# UniversalPPU.net
KiCad netlist of a schematic drawn in EAGLE
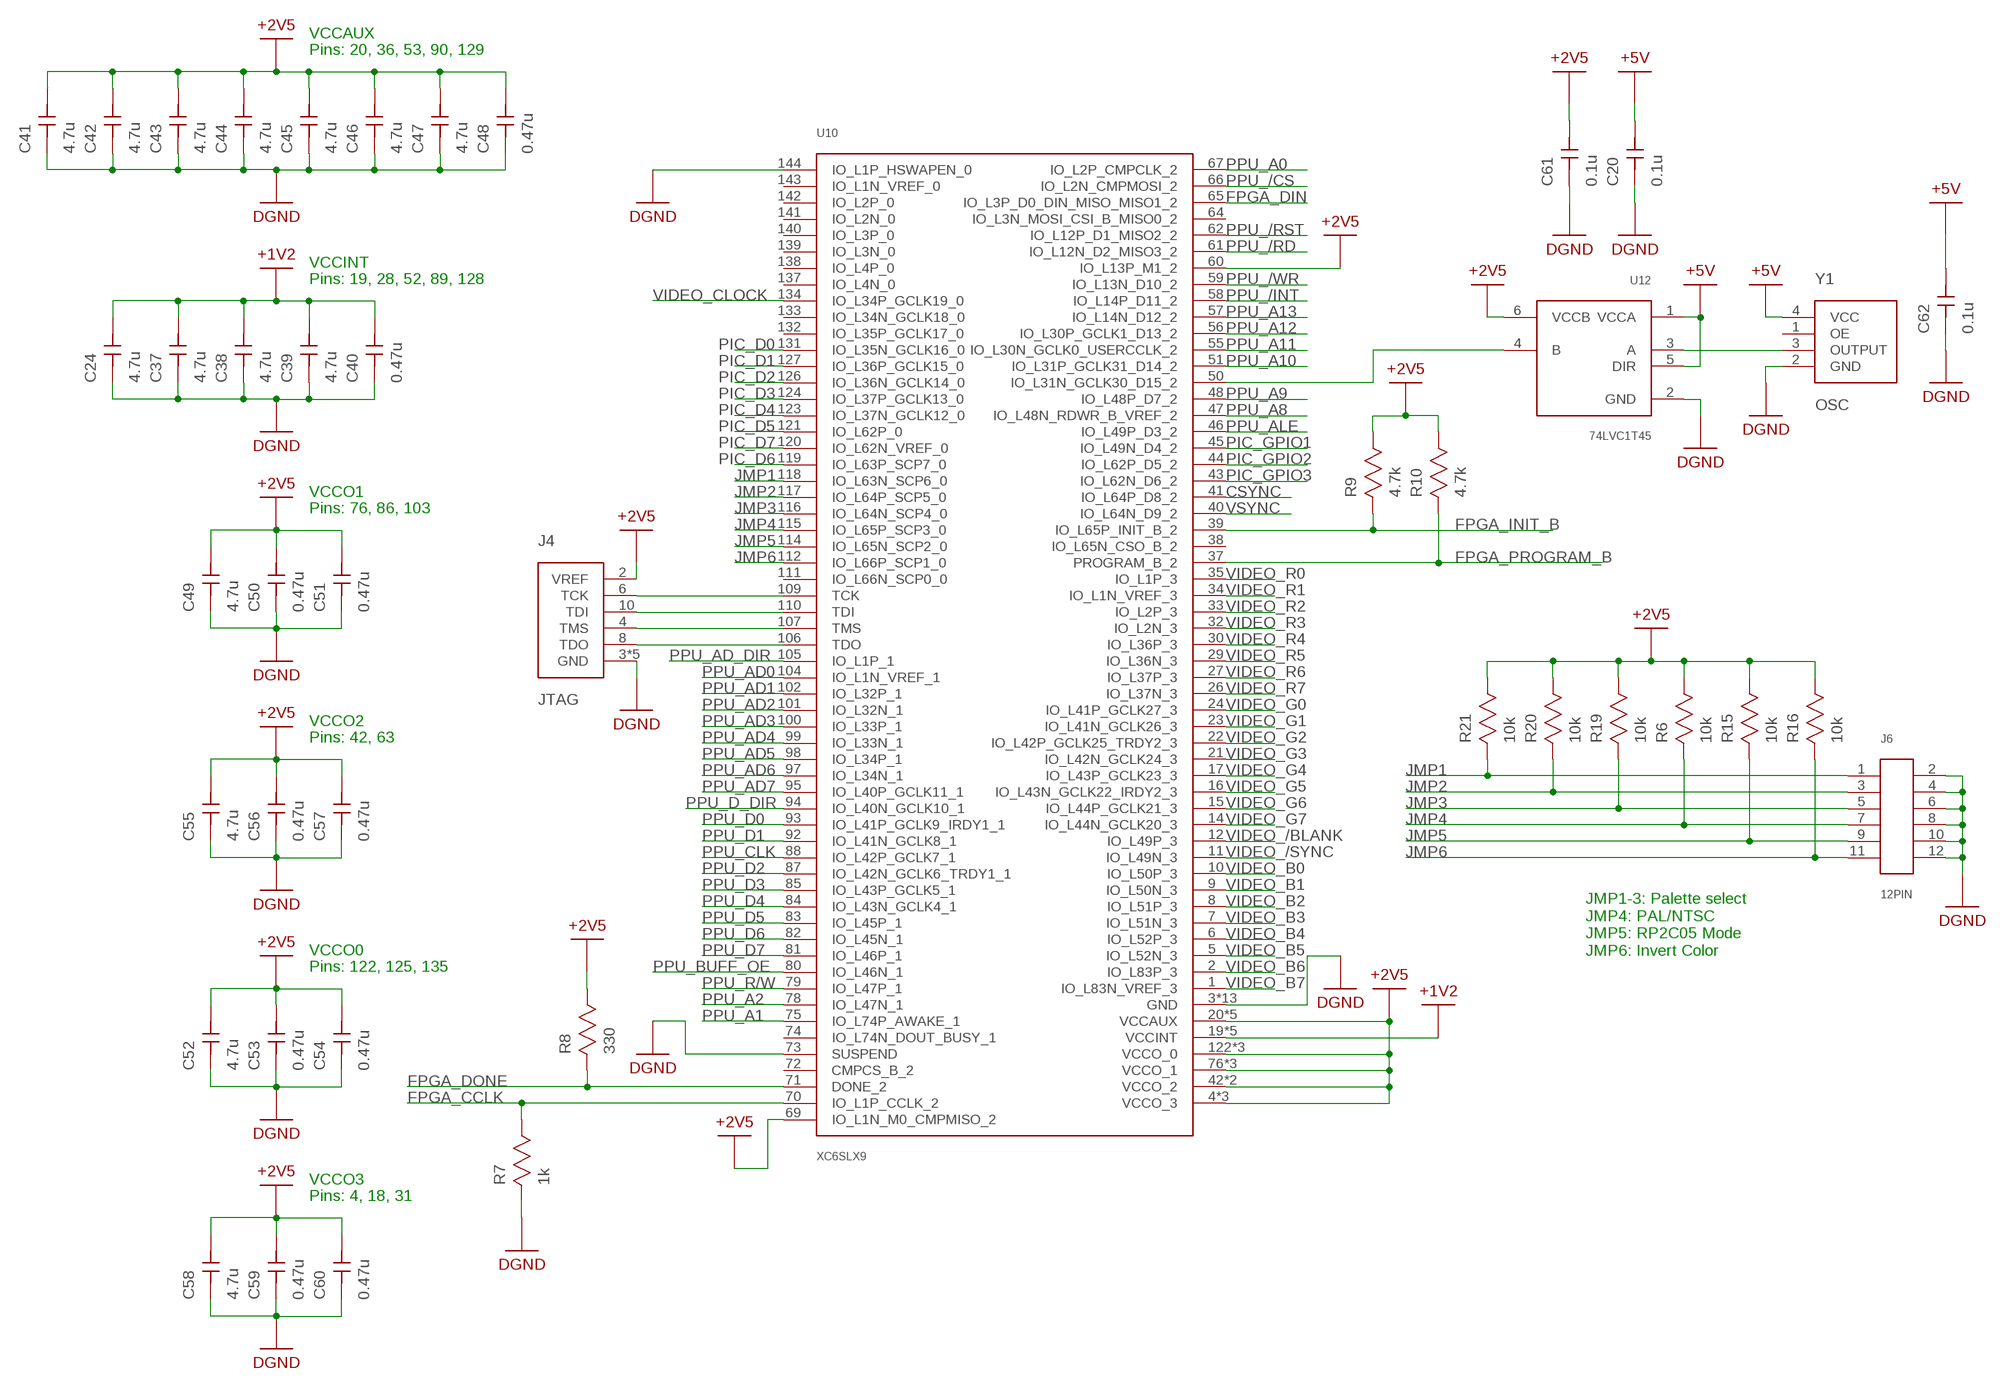
[diagram p0: schematic, sheet 1]
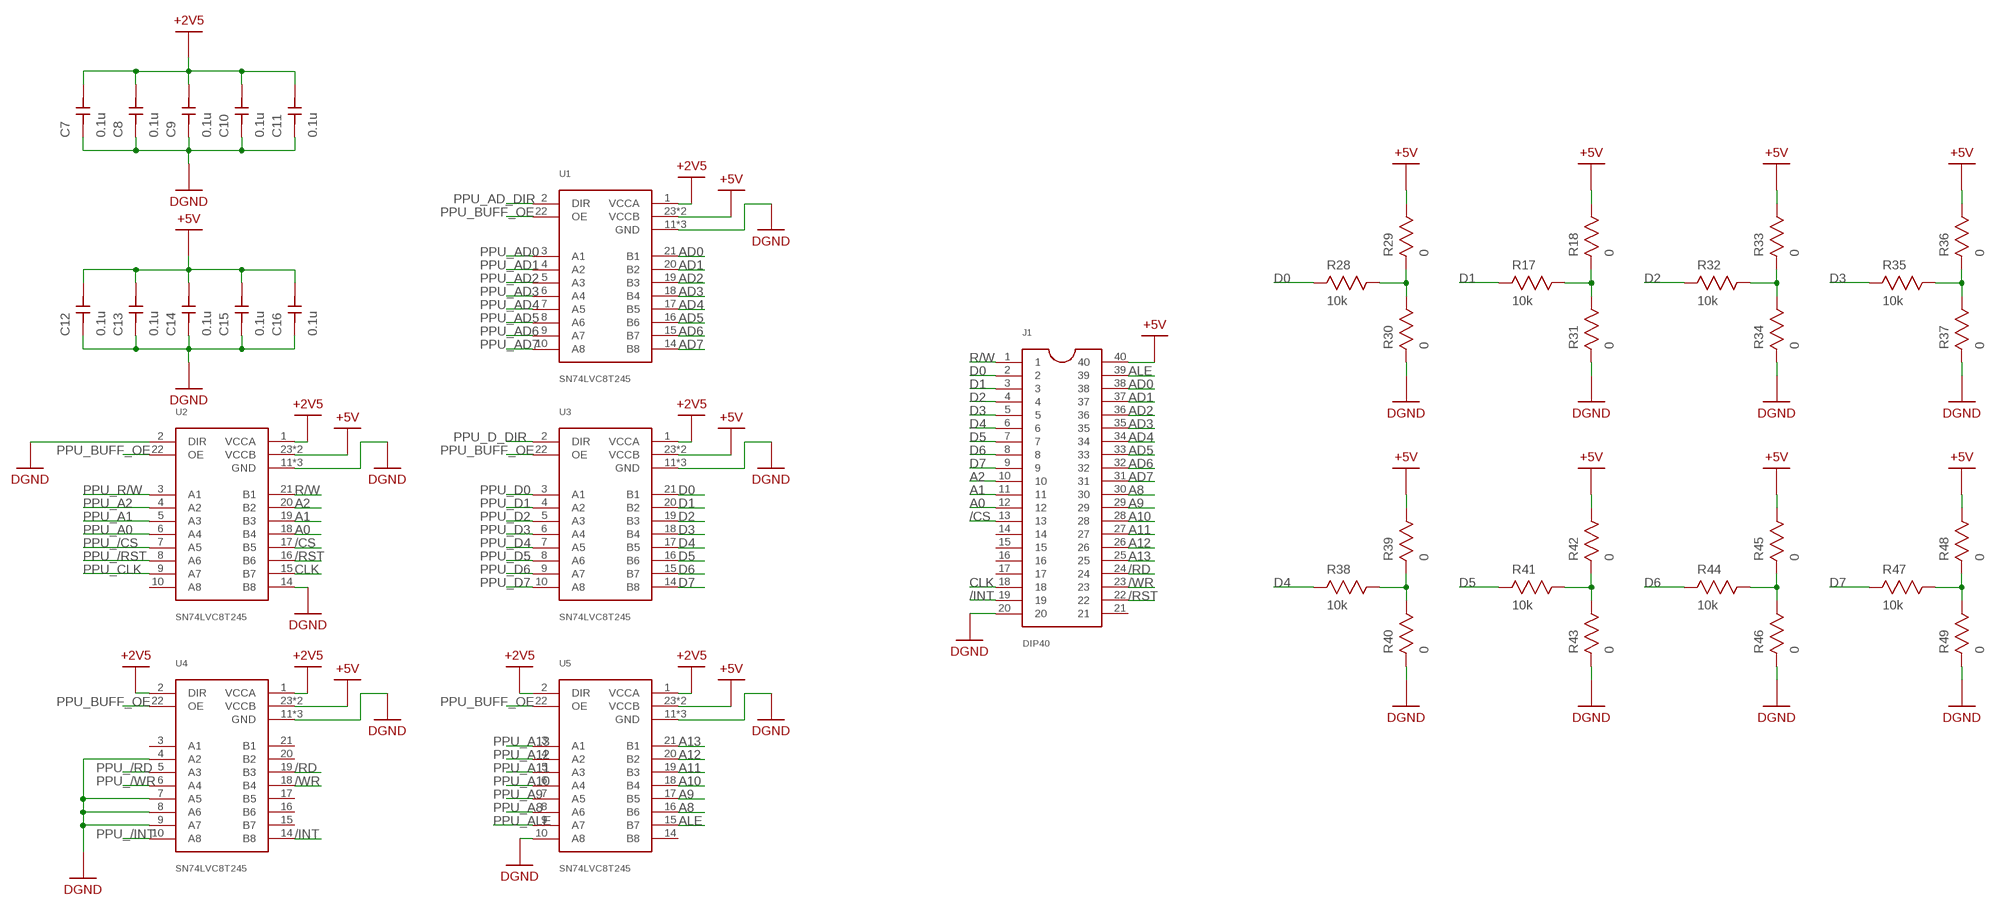
[diagram p1: schematic, sheet 2]
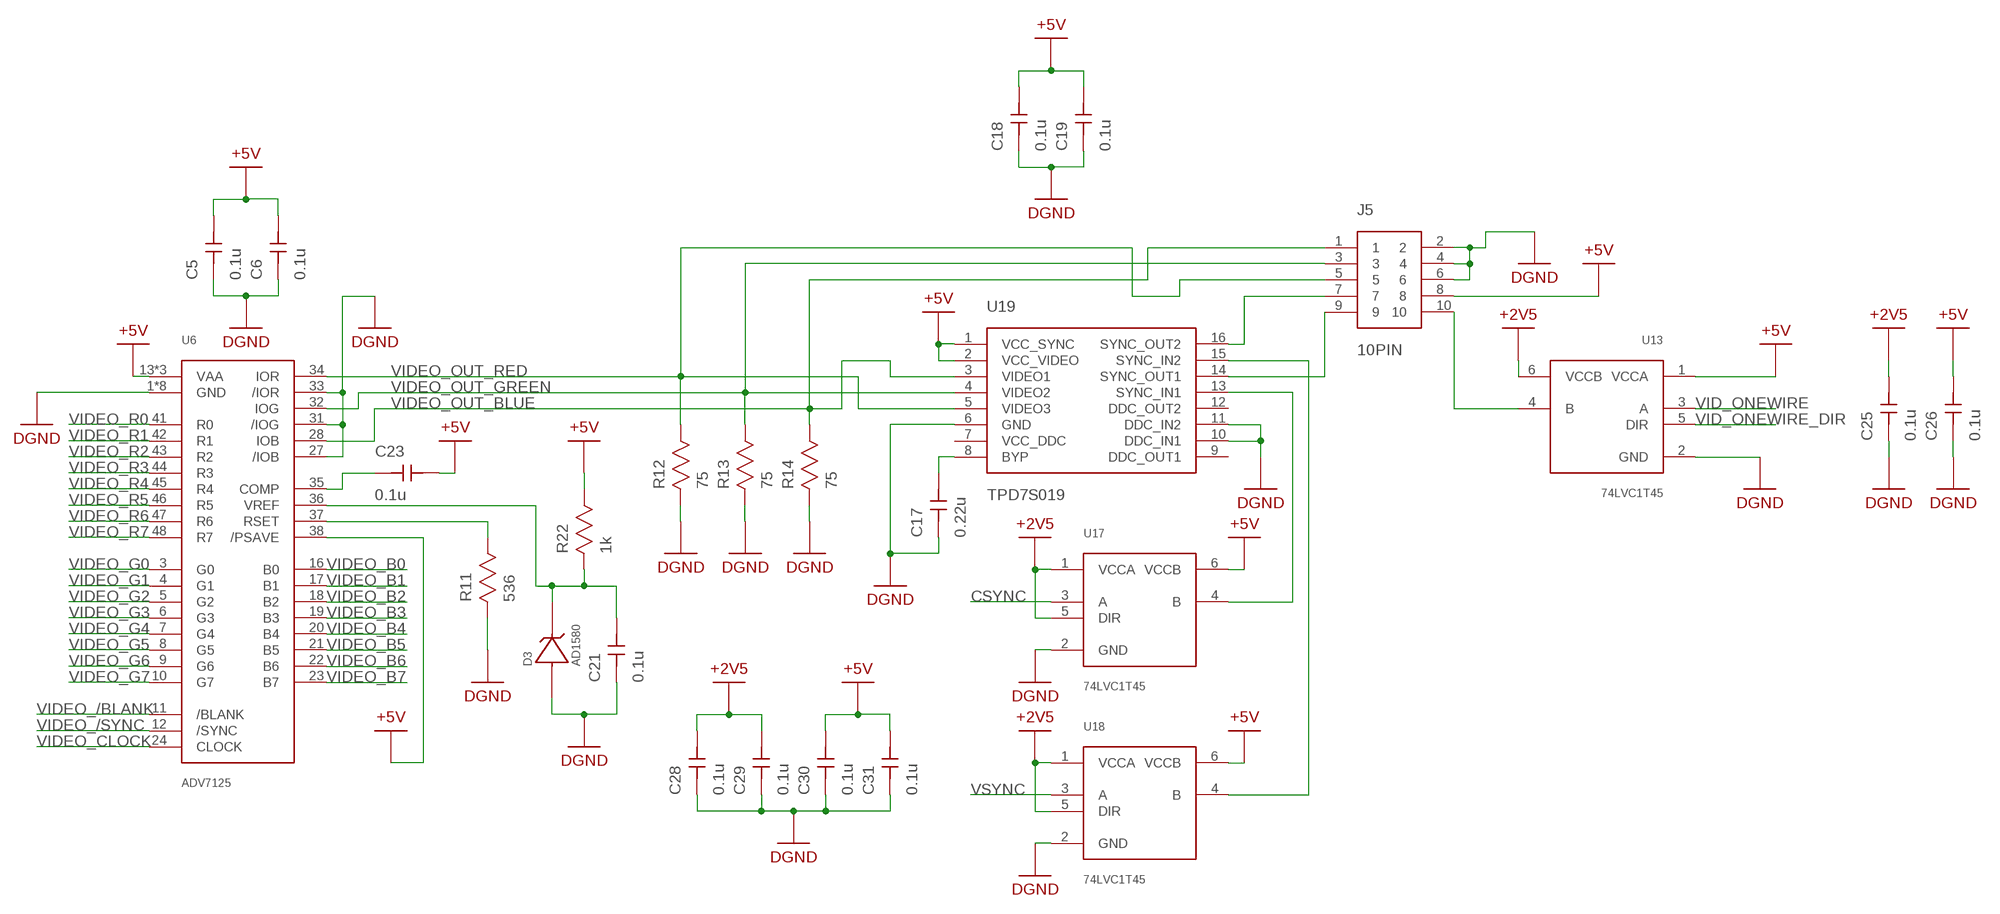
[diagram p2: schematic, sheet 3]
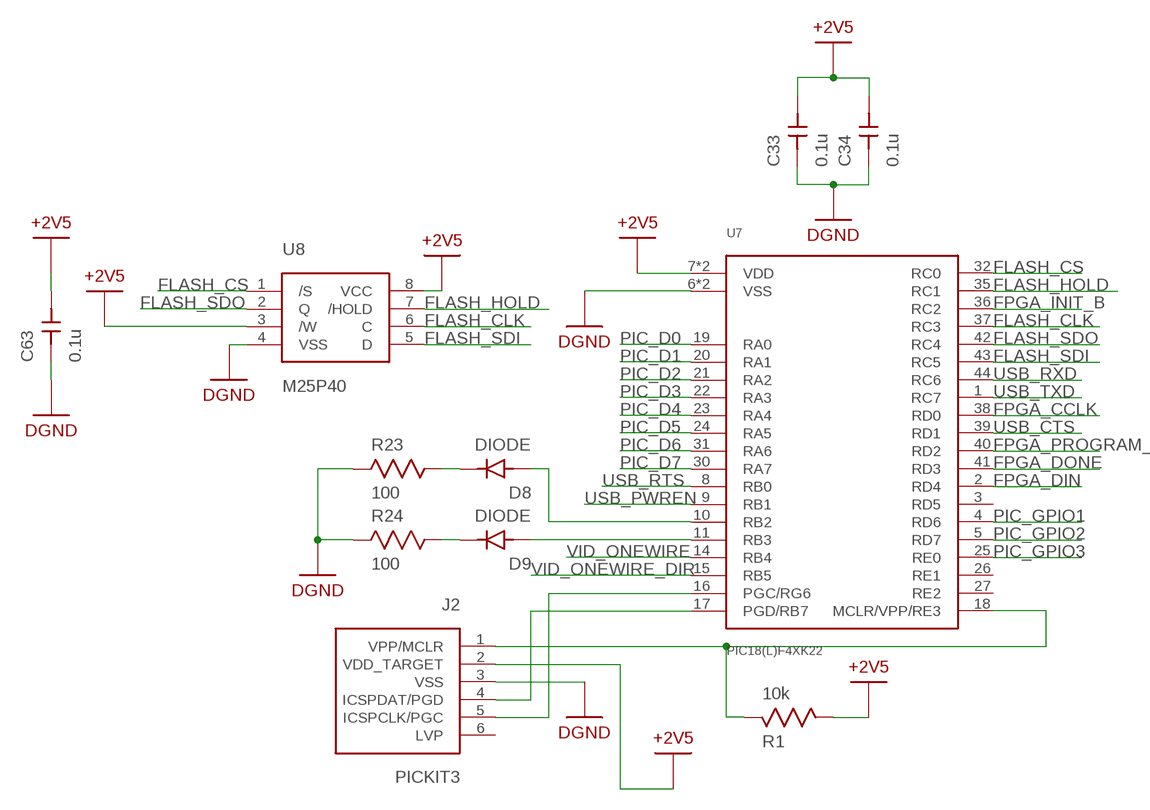
[diagram p3: schematic, sheet 4]
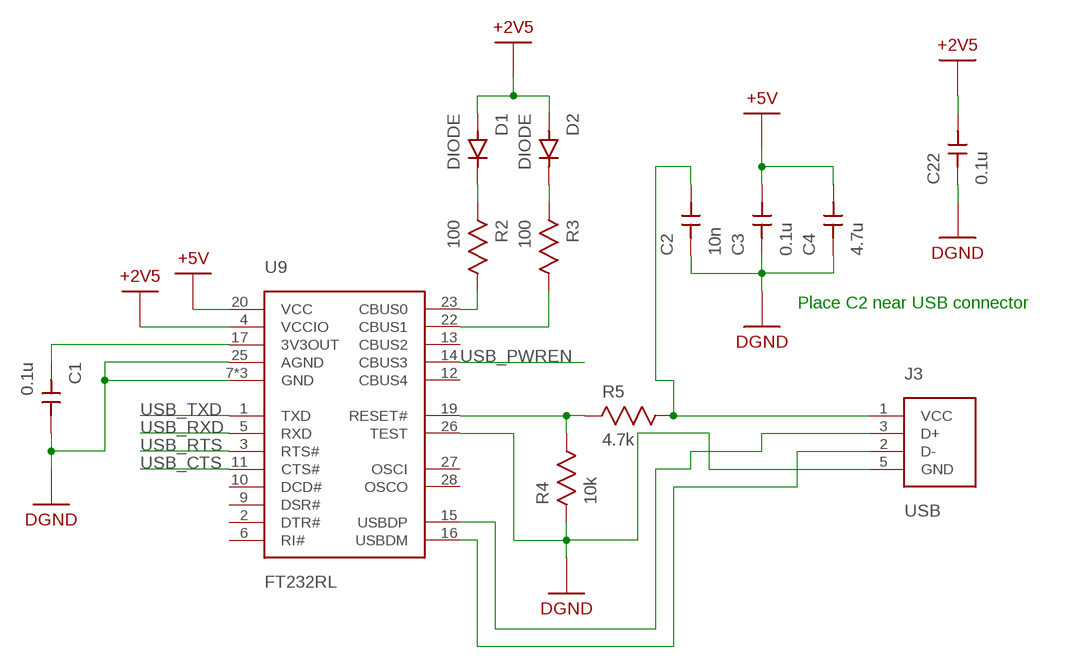
[diagram p4: schematic, sheet 5]
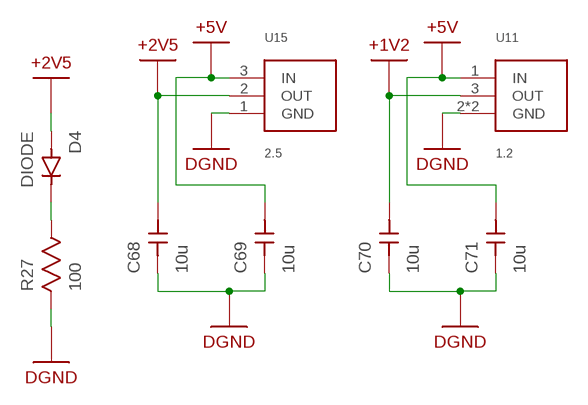
[diagram p5: schematic, sheet 6]

(export (version "E")
  (design (tool "Eeschema 10.0.6"))
  (components
    (comp (ref "C5")
      (value "0.1u")
      (footprint "eagle-import:TDK_C0816")
      (libsource (lib "eagle-import") (part "CAPACITORTDK_C0816"))
    )
    (comp (ref "C6")
      (value "0.1u")
      (footprint "eagle-import:TDK_C0816")
      (libsource (lib "eagle-import") (part "CAPACITORTDK_C0816"))
    )
    (comp (ref "C17")
      (value "0.22u")
      (footprint "eagle-import:TDK_C0816")
      (libsource (lib "eagle-import") (part "CAPACITORTDK_C0816"))
    )
    (comp (ref "C18")
      (value "0.1u")
      (footprint "eagle-import:TDK_C0816")
      (libsource (lib "eagle-import") (part "CAPACITORTDK_C0816"))
    )
    (comp (ref "C19")
      (value "0.1u")
      (footprint "eagle-import:TDK_C0816")
      (libsource (lib "eagle-import") (part "CAPACITORTDK_C0816"))
    )
    (comp (ref "C21")
      (value "0.1u")
      (footprint "eagle-import:TDK_C0816")
      (libsource (lib "eagle-import") (part "CAPACITORTDK_C0816"))
    )
    (comp (ref "C23")
      (value "0.1u")
      (footprint "eagle-import:TDK_C0816")
      (libsource (lib "eagle-import") (part "CAPACITORTDK_C0816"))
    )
    (comp (ref "C25")
      (value "0.1u")
      (footprint "eagle-import:TDK_C0816")
      (libsource (lib "eagle-import") (part "CAPACITORTDK_C0816"))
    )
    (comp (ref "C26")
      (value "0.1u")
      (footprint "eagle-import:TDK_C0816")
      (libsource (lib "eagle-import") (part "CAPACITORTDK_C0816"))
    )
    (comp (ref "C28")
      (value "0.1u")
      (footprint "eagle-import:TDK_C0816")
      (libsource (lib "eagle-import") (part "CAPACITORTDK_C0816"))
    )
    (comp (ref "C29")
      (value "0.1u")
      (footprint "eagle-import:TDK_C0816")
      (libsource (lib "eagle-import") (part "CAPACITORTDK_C0816"))
    )
    (comp (ref "C30")
      (value "0.1u")
      (footprint "eagle-import:TDK_C0816")
      (libsource (lib "eagle-import") (part "CAPACITORTDK_C0816"))
    )
    (comp (ref "C31")
      (value "0.1u")
      (footprint "eagle-import:TDK_C0816")
      (libsource (lib "eagle-import") (part "CAPACITORTDK_C0816"))
    )
    (comp (ref "D3")
      (value "AD1580")
      (footprint "eagle-import:SOT-23-3")
      (libsource (lib "eagle-import") (part "AD1580"))
    )
    (comp (ref "J5")
      (value "10PIN")
      (footprint "eagle-import:10PIN")
      (libsource (lib "eagle-import") (part "10PIN"))
    )
    (comp (ref "R11")
      (value "536")
      (footprint "eagle-import:0603")
      (libsource (lib "eagle-import") (part "RESISTOR0603"))
    )
    (comp (ref "R12")
      (value "75")
      (footprint "eagle-import:0603")
      (libsource (lib "eagle-import") (part "RESISTOR0603"))
    )
    (comp (ref "R13")
      (value "75")
      (footprint "eagle-import:0603")
      (libsource (lib "eagle-import") (part "RESISTOR0603"))
    )
    (comp (ref "R14")
      (value "75")
      (footprint "eagle-import:0603")
      (libsource (lib "eagle-import") (part "RESISTOR0603"))
    )
    (comp (ref "R22")
      (value "1k")
      (footprint "eagle-import:0603")
      (libsource (lib "eagle-import") (part "RESISTOR0603"))
    )
    (comp (ref "U6")
      (value "ADV7125")
      (footprint "eagle-import:LQFP-48")
      (libsource (lib "eagle-import") (part "ADV7125"))
    )
    (comp (ref "U13")
      (value "74LVC1T45")
      (footprint "eagle-import:R-PDSO-G6")
      (libsource (lib "eagle-import") (part "74LVC1T45"))
    )
    (comp (ref "U17")
      (value "74LVC1T45")
      (footprint "eagle-import:R-PDSO-G6")
      (libsource (lib "eagle-import") (part "74LVC1T45"))
    )
    (comp (ref "U18")
      (value "74LVC1T45")
      (footprint "eagle-import:R-PDSO-G6")
      (libsource (lib "eagle-import") (part "74LVC1T45"))
    )
    (comp (ref "U19")
      (value "TPD7S019")
      (footprint "eagle-import:R-PDSO-G16")
      (libsource (lib "eagle-import") (part "TPD7S019"))
    )
    (comp (ref "C20")
      (value "0.1u")
      (footprint "eagle-import:TDK_C0816")
      (libsource (lib "eagle-import") (part "CAPACITORTDK_C0816"))
    )
    (comp (ref "C24")
      (value "4.7u")
      (footprint "eagle-import:TDK_C0816")
      (libsource (lib "eagle-import") (part "CAPACITORTDK_C0816"))
    )
    (comp (ref "C37")
      (value "4.7u")
      (footprint "eagle-import:TDK_C0816")
      (libsource (lib "eagle-import") (part "CAPACITORTDK_C0816"))
    )
    (comp (ref "C38")
      (value "4.7u")
      (footprint "eagle-import:TDK_C0816")
      (libsource (lib "eagle-import") (part "CAPACITORTDK_C0816"))
    )
    (comp (ref "C39")
      (value "4.7u")
      (footprint "eagle-import:TDK_C0816")
      (libsource (lib "eagle-import") (part "CAPACITORTDK_C0816"))
    )
    (comp (ref "C40")
      (value "0.47u")
      (footprint "eagle-import:TDK_C0816")
      (libsource (lib "eagle-import") (part "CAPACITORTDK_C0816"))
    )
    (comp (ref "C41")
      (value "4.7u")
      (footprint "eagle-import:TDK_C0816")
      (libsource (lib "eagle-import") (part "CAPACITORTDK_C0816"))
    )
    (comp (ref "C42")
      (value "4.7u")
      (footprint "eagle-import:TDK_C0816")
      (libsource (lib "eagle-import") (part "CAPACITORTDK_C0816"))
    )
    (comp (ref "C43")
      (value "4.7u")
      (footprint "eagle-import:TDK_C0816")
      (libsource (lib "eagle-import") (part "CAPACITORTDK_C0816"))
    )
    (comp (ref "C44")
      (value "4.7u")
      (footprint "eagle-import:TDK_C0816")
      (libsource (lib "eagle-import") (part "CAPACITORTDK_C0816"))
    )
    (comp (ref "C45")
      (value "4.7u")
      (footprint "eagle-import:TDK_C0816")
      (libsource (lib "eagle-import") (part "CAPACITORTDK_C0816"))
    )
    (comp (ref "C46")
      (value "4.7u")
      (footprint "eagle-import:TDK_C0816")
      (libsource (lib "eagle-import") (part "CAPACITORTDK_C0816"))
    )
    (comp (ref "C47")
      (value "4.7u")
      (footprint "eagle-import:TDK_C0816")
      (libsource (lib "eagle-import") (part "CAPACITORTDK_C0816"))
    )
    (comp (ref "C48")
      (value "0.47u")
      (footprint "eagle-import:TDK_C0816")
      (libsource (lib "eagle-import") (part "CAPACITORTDK_C0816"))
    )
    (comp (ref "C49")
      (value "4.7u")
      (footprint "eagle-import:TDK_C0816")
      (libsource (lib "eagle-import") (part "CAPACITORTDK_C0816"))
    )
    (comp (ref "C50")
      (value "0.47u")
      (footprint "eagle-import:TDK_C0816")
      (libsource (lib "eagle-import") (part "CAPACITORTDK_C0816"))
    )
    (comp (ref "C51")
      (value "0.47u")
      (footprint "eagle-import:TDK_C0816")
      (libsource (lib "eagle-import") (part "CAPACITORTDK_C0816"))
    )
    (comp (ref "C52")
      (value "4.7u")
      (footprint "eagle-import:TDK_C0816")
      (libsource (lib "eagle-import") (part "CAPACITORTDK_C0816"))
    )
    (comp (ref "C53")
      (value "0.47u")
      (footprint "eagle-import:TDK_C0816")
      (libsource (lib "eagle-import") (part "CAPACITORTDK_C0816"))
    )
    (comp (ref "C54")
      (value "0.47u")
      (footprint "eagle-import:TDK_C0816")
      (libsource (lib "eagle-import") (part "CAPACITORTDK_C0816"))
    )
    (comp (ref "C55")
      (value "4.7u")
      (footprint "eagle-import:TDK_C0816")
      (libsource (lib "eagle-import") (part "CAPACITORTDK_C0816"))
    )
    (comp (ref "C56")
      (value "0.47u")
      (footprint "eagle-import:TDK_C0816")
      (libsource (lib "eagle-import") (part "CAPACITORTDK_C0816"))
    )
    (comp (ref "C57")
      (value "0.47u")
      (footprint "eagle-import:TDK_C0816")
      (libsource (lib "eagle-import") (part "CAPACITORTDK_C0816"))
    )
    (comp (ref "C58")
      (value "4.7u")
      (footprint "eagle-import:TDK_C0816")
      (libsource (lib "eagle-import") (part "CAPACITORTDK_C0816"))
    )
    (comp (ref "C59")
      (value "0.47u")
      (footprint "eagle-import:TDK_C0816")
      (libsource (lib "eagle-import") (part "CAPACITORTDK_C0816"))
    )
    (comp (ref "C60")
      (value "0.47u")
      (footprint "eagle-import:TDK_C0816")
      (libsource (lib "eagle-import") (part "CAPACITORTDK_C0816"))
    )
    (comp (ref "C61")
      (value "0.1u")
      (footprint "eagle-import:TDK_C0816")
      (libsource (lib "eagle-import") (part "CAPACITORTDK_C0816"))
    )
    (comp (ref "C62")
      (value "0.1u")
      (footprint "eagle-import:TDK_C0816")
      (libsource (lib "eagle-import") (part "CAPACITORTDK_C0816"))
    )
    (comp (ref "J4")
      (value "JTAG")
      (footprint "eagle-import:14PIN_2MM")
      (libsource (lib "eagle-import") (part "JTAG"))
    )
    (comp (ref "J6")
      (value "12PIN")
      (footprint "eagle-import:12PIN")
      (libsource (lib "eagle-import") (part "12PIN"))
    )
    (comp (ref "R6")
      (value "10k")
      (footprint "eagle-import:0603")
      (libsource (lib "eagle-import") (part "RESISTOR0603"))
    )
    (comp (ref "R7")
      (value "1k")
      (footprint "eagle-import:0603")
      (libsource (lib "eagle-import") (part "RESISTOR0603"))
    )
    (comp (ref "R8")
      (value "330")
      (footprint "eagle-import:0603")
      (libsource (lib "eagle-import") (part "RESISTOR0603"))
    )
    (comp (ref "R9")
      (value "4.7k")
      (footprint "eagle-import:0603")
      (libsource (lib "eagle-import") (part "RESISTOR0603"))
    )
    (comp (ref "R10")
      (value "4.7k")
      (footprint "eagle-import:0603")
      (libsource (lib "eagle-import") (part "RESISTOR0603"))
    )
    (comp (ref "R15")
      (value "10k")
      (footprint "eagle-import:0603")
      (libsource (lib "eagle-import") (part "RESISTOR0603"))
    )
    (comp (ref "R16")
      (value "10k")
      (footprint "eagle-import:0603")
      (libsource (lib "eagle-import") (part "RESISTOR0603"))
    )
    (comp (ref "R19")
      (value "10k")
      (footprint "eagle-import:0603")
      (libsource (lib "eagle-import") (part "RESISTOR0603"))
    )
    (comp (ref "R20")
      (value "10k")
      (footprint "eagle-import:0603")
      (libsource (lib "eagle-import") (part "RESISTOR0603"))
    )
    (comp (ref "R21")
      (value "10k")
      (footprint "eagle-import:0603")
      (libsource (lib "eagle-import") (part "RESISTOR0603"))
    )
    (comp (ref "U10")
      (value "XC6SLX9")
      (footprint "eagle-import:TQG144")
      (libsource (lib "eagle-import") (part "XC6SLX9"))
    )
    (comp (ref "U12")
      (value "74LVC1T45")
      (footprint "eagle-import:R-PDSO-G6")
      (libsource (lib "eagle-import") (part "74LVC1T45"))
    )
    (comp (ref "Y1")
      (value "OSC")
      (footprint "eagle-import:OSC")
      (libsource (lib "eagle-import") (part "OSC"))
    )
    (comp (ref "C68")
      (value "10u")
      (footprint "eagle-import:TDK_C1632")
      (libsource (lib "eagle-import") (part "CAPACITORTDK_C1632"))
    )
    (comp (ref "C69")
      (value "10u")
      (footprint "eagle-import:TDK_C1632")
      (libsource (lib "eagle-import") (part "CAPACITORTDK_C1632"))
    )
    (comp (ref "C70")
      (value "10u")
      (footprint "eagle-import:TDK_C1632")
      (libsource (lib "eagle-import") (part "CAPACITORTDK_C1632"))
    )
    (comp (ref "C71")
      (value "10u")
      (footprint "eagle-import:TDK_C1632")
      (libsource (lib "eagle-import") (part "CAPACITORTDK_C1632"))
    )
    (comp (ref "D4")
      (value "DIODE")
      (footprint "eagle-import:LED_0603")
      (libsource (lib "eagle-import") (part "DIODE"))
    )
    (comp (ref "R27")
      (value "100")
      (footprint "eagle-import:0603")
      (libsource (lib "eagle-import") (part "RESISTOR0603"))
    )
    (comp (ref "U11")
      (value "1.2")
      (footprint "eagle-import:SOT-223")
      (libsource (lib "eagle-import") (part "NCP566"))
    )
    (comp (ref "U15")
      (value "2.5")
      (footprint "eagle-import:SOT-223")
      (libsource (lib "eagle-import") (part "NCP1117"))
    )
    (comp (ref "C7")
      (value "0.1u")
      (footprint "eagle-import:TDK_C0816")
      (libsource (lib "eagle-import") (part "CAPACITORTDK_C0816"))
    )
    (comp (ref "C8")
      (value "0.1u")
      (footprint "eagle-import:TDK_C0816")
      (libsource (lib "eagle-import") (part "CAPACITORTDK_C0816"))
    )
    (comp (ref "C9")
      (value "0.1u")
      (footprint "eagle-import:TDK_C0816")
      (libsource (lib "eagle-import") (part "CAPACITORTDK_C0816"))
    )
    (comp (ref "C10")
      (value "0.1u")
      (footprint "eagle-import:TDK_C0816")
      (libsource (lib "eagle-import") (part "CAPACITORTDK_C0816"))
    )
    (comp (ref "C11")
      (value "0.1u")
      (footprint "eagle-import:TDK_C0816")
      (libsource (lib "eagle-import") (part "CAPACITORTDK_C0816"))
    )
    (comp (ref "C12")
      (value "0.1u")
      (footprint "eagle-import:TDK_C0816")
      (libsource (lib "eagle-import") (part "CAPACITORTDK_C0816"))
    )
    (comp (ref "C13")
      (value "0.1u")
      (footprint "eagle-import:TDK_C0816")
      (libsource (lib "eagle-import") (part "CAPACITORTDK_C0816"))
    )
    (comp (ref "C14")
      (value "0.1u")
      (footprint "eagle-import:TDK_C0816")
      (libsource (lib "eagle-import") (part "CAPACITORTDK_C0816"))
    )
    (comp (ref "C15")
      (value "0.1u")
      (footprint "eagle-import:TDK_C0816")
      (libsource (lib "eagle-import") (part "CAPACITORTDK_C0816"))
    )
    (comp (ref "C16")
      (value "0.1u")
      (footprint "eagle-import:TDK_C0816")
      (libsource (lib "eagle-import") (part "CAPACITORTDK_C0816"))
    )
    (comp (ref "J1")
      (value "DIP40")
      (footprint "eagle-import:DIP40")
      (libsource (lib "eagle-import") (part "DIP40"))
    )
    (comp (ref "R17")
      (value "10k")
      (footprint "eagle-import:0603")
      (libsource (lib "eagle-import") (part "RESISTOR0603"))
    )
    (comp (ref "R18")
      (value "0")
      (footprint "eagle-import:0603")
      (libsource (lib "eagle-import") (part "RESISTOR0603"))
    )
    (comp (ref "R28")
      (value "10k")
      (footprint "eagle-import:0603")
      (libsource (lib "eagle-import") (part "RESISTOR0603"))
    )
    (comp (ref "R29")
      (value "0")
      (footprint "eagle-import:0603")
      (libsource (lib "eagle-import") (part "RESISTOR0603"))
    )
    (comp (ref "R30")
      (value "0")
      (footprint "eagle-import:0603")
      (libsource (lib "eagle-import") (part "RESISTOR0603"))
    )
    (comp (ref "R31")
      (value "0")
      (footprint "eagle-import:0603")
      (libsource (lib "eagle-import") (part "RESISTOR0603"))
    )
    (comp (ref "R32")
      (value "10k")
      (footprint "eagle-import:0603")
      (libsource (lib "eagle-import") (part "RESISTOR0603"))
    )
    (comp (ref "R33")
      (value "0")
      (footprint "eagle-import:0603")
      (libsource (lib "eagle-import") (part "RESISTOR0603"))
    )
    (comp (ref "R34")
      (value "0")
      (footprint "eagle-import:0603")
      (libsource (lib "eagle-import") (part "RESISTOR0603"))
    )
    (comp (ref "R35")
      (value "10k")
      (footprint "eagle-import:0603")
      (libsource (lib "eagle-import") (part "RESISTOR0603"))
    )
    (comp (ref "R36")
      (value "0")
      (footprint "eagle-import:0603")
      (libsource (lib "eagle-import") (part "RESISTOR0603"))
    )
    (comp (ref "R37")
      (value "0")
      (footprint "eagle-import:0603")
      (libsource (lib "eagle-import") (part "RESISTOR0603"))
    )
    (comp (ref "R38")
      (value "10k")
      (footprint "eagle-import:0603")
      (libsource (lib "eagle-import") (part "RESISTOR0603"))
    )
    (comp (ref "R39")
      (value "0")
      (footprint "eagle-import:0603")
      (libsource (lib "eagle-import") (part "RESISTOR0603"))
    )
    (comp (ref "R40")
      (value "0")
      (footprint "eagle-import:0603")
      (libsource (lib "eagle-import") (part "RESISTOR0603"))
    )
    (comp (ref "R41")
      (value "10k")
      (footprint "eagle-import:0603")
      (libsource (lib "eagle-import") (part "RESISTOR0603"))
    )
    (comp (ref "R42")
      (value "0")
      (footprint "eagle-import:0603")
      (libsource (lib "eagle-import") (part "RESISTOR0603"))
    )
    (comp (ref "R43")
      (value "0")
      (footprint "eagle-import:0603")
      (libsource (lib "eagle-import") (part "RESISTOR0603"))
    )
    (comp (ref "R44")
      (value "10k")
      (footprint "eagle-import:0603")
      (libsource (lib "eagle-import") (part "RESISTOR0603"))
    )
    (comp (ref "R45")
      (value "0")
      (footprint "eagle-import:0603")
      (libsource (lib "eagle-import") (part "RESISTOR0603"))
    )
    (comp (ref "R46")
      (value "0")
      (footprint "eagle-import:0603")
      (libsource (lib "eagle-import") (part "RESISTOR0603"))
    )
    (comp (ref "R47")
      (value "10k")
      (footprint "eagle-import:0603")
      (libsource (lib "eagle-import") (part "RESISTOR0603"))
    )
    (comp (ref "R48")
      (value "0")
      (footprint "eagle-import:0603")
      (libsource (lib "eagle-import") (part "RESISTOR0603"))
    )
    (comp (ref "R49")
      (value "0")
      (footprint "eagle-import:0603")
      (libsource (lib "eagle-import") (part "RESISTOR0603"))
    )
    (comp (ref "U1")
      (value "SN74LVC8T245")
      (footprint "eagle-import:TSSOP24")
      (libsource (lib "eagle-import") (part "SN74LVC8T245"))
    )
    (comp (ref "U2")
      (value "SN74LVC8T245")
      (footprint "eagle-import:TSSOP24")
      (libsource (lib "eagle-import") (part "SN74LVC8T245"))
    )
    (comp (ref "U3")
      (value "SN74LVC8T245")
      (footprint "eagle-import:TSSOP24")
      (libsource (lib "eagle-import") (part "SN74LVC8T245"))
    )
    (comp (ref "U4")
      (value "SN74LVC8T245")
      (footprint "eagle-import:TSSOP24")
      (libsource (lib "eagle-import") (part "SN74LVC8T245"))
    )
    (comp (ref "U5")
      (value "SN74LVC8T245")
      (footprint "eagle-import:TSSOP24")
      (libsource (lib "eagle-import") (part "SN74LVC8T245"))
    )
    (comp (ref "C1")
      (value "0.1u")
      (footprint "eagle-import:TDK_C0816")
      (libsource (lib "eagle-import") (part "CAPACITORTDK_C0816"))
    )
    (comp (ref "C2")
      (value "10n")
      (footprint "eagle-import:TDK_C0816")
      (libsource (lib "eagle-import") (part "CAPACITORTDK_C0816"))
    )
    (comp (ref "C3")
      (value "0.1u")
      (footprint "eagle-import:TDK_C0816")
      (libsource (lib "eagle-import") (part "CAPACITORTDK_C0816"))
    )
    (comp (ref "C4")
      (value "4.7u")
      (footprint "eagle-import:TDK_C0816")
      (libsource (lib "eagle-import") (part "CAPACITORTDK_C0816"))
    )
    (comp (ref "C22")
      (value "0.1u")
      (footprint "eagle-import:TDK_C0816")
      (libsource (lib "eagle-import") (part "CAPACITORTDK_C0816"))
    )
    (comp (ref "D1")
      (value "DIODE")
      (footprint "eagle-import:LED_0603")
      (libsource (lib "eagle-import") (part "DIODE"))
    )
    (comp (ref "D2")
      (value "DIODE")
      (footprint "eagle-import:LED_0603")
      (libsource (lib "eagle-import") (part "DIODE"))
    )
    (comp (ref "J3")
      (value "USB")
      (footprint "eagle-import:USB")
      (libsource (lib "eagle-import") (part "USB"))
    )
    (comp (ref "R2")
      (value "100")
      (footprint "eagle-import:0603")
      (libsource (lib "eagle-import") (part "RESISTOR0603"))
    )
    (comp (ref "R3")
      (value "100")
      (footprint "eagle-import:0603")
      (libsource (lib "eagle-import") (part "RESISTOR0603"))
    )
    (comp (ref "R4")
      (value "10k")
      (footprint "eagle-import:0603")
      (libsource (lib "eagle-import") (part "RESISTOR0603"))
    )
    (comp (ref "R5")
      (value "4.7k")
      (footprint "eagle-import:0603")
      (libsource (lib "eagle-import") (part "RESISTOR0603"))
    )
    (comp (ref "U9")
      (value "FT232RL")
      (footprint "eagle-import:SSOP-28")
      (libsource (lib "eagle-import") (part "FT232RL"))
    )
    (comp (ref "C33")
      (value "0.1u")
      (footprint "eagle-import:TDK_C0816")
      (libsource (lib "eagle-import") (part "CAPACITORTDK_C0816"))
    )
    (comp (ref "C34")
      (value "0.1u")
      (footprint "eagle-import:TDK_C0816")
      (libsource (lib "eagle-import") (part "CAPACITORTDK_C0816"))
    )
    (comp (ref "C63")
      (value "0.1u")
      (footprint "eagle-import:TDK_C0816")
      (libsource (lib "eagle-import") (part "CAPACITORTDK_C0816"))
    )
    (comp (ref "D8")
      (value "DIODE")
      (footprint "eagle-import:LED_0603")
      (libsource (lib "eagle-import") (part "DIODE"))
    )
    (comp (ref "D9")
      (value "DIODE")
      (footprint "eagle-import:LED_0603")
      (libsource (lib "eagle-import") (part "DIODE"))
    )
    (comp (ref "J2")
      (value "PICKIT3")
      (footprint "eagle-import:6SIP")
      (libsource (lib "eagle-import") (part "PICKIT3"))
    )
    (comp (ref "R1")
      (value "10k")
      (footprint "eagle-import:0603")
      (libsource (lib "eagle-import") (part "RESISTOR0603"))
    )
    (comp (ref "R23")
      (value "100")
      (footprint "eagle-import:0603")
      (libsource (lib "eagle-import") (part "RESISTOR0603"))
    )
    (comp (ref "R24")
      (value "100")
      (footprint "eagle-import:0603")
      (libsource (lib "eagle-import") (part "RESISTOR0603"))
    )
    (comp (ref "U7")
      (value "PIC18(L)F4XK22")
      (footprint "eagle-import:TQFP44")
      (libsource (lib "eagle-import") (part "PIC18(L)F4XK22"))
    )
    (comp (ref "U8")
      (value "M25P40")
      (footprint "eagle-import:8PIN")
      (libsource (lib "eagle-import") (part "M25P40"))
    )
  )
  (nets
    (net (code "1") (name "+1V2") (class "Default")
      (node (ref "C24") (pin "2") (pinfunction "P$2_2") (pintype "bidirectional"))
      (node (ref "C37") (pin "2") (pinfunction "P$2_2") (pintype "bidirectional"))
      (node (ref "C38") (pin "2") (pinfunction "P$2_2") (pintype "bidirectional"))
      (node (ref "C39") (pin "2") (pinfunction "P$2_2") (pintype "bidirectional"))
      (node (ref "C40") (pin "2") (pinfunction "P$2_2") (pintype "bidirectional"))
      (node (ref "C70") (pin "2") (pinfunction "P$2_2") (pintype "bidirectional"))
      (node (ref "U10") (pin "128") (pinfunction "VCCINT_128") (pintype "bidirectional"))
      (node (ref "U10") (pin "19") (pinfunction "VCCINT_19") (pintype "bidirectional"))
      (node (ref "U10") (pin "28") (pinfunction "VCCINT_28") (pintype "bidirectional"))
      (node (ref "U10") (pin "52") (pinfunction "VCCINT_52") (pintype "bidirectional"))
      (node (ref "U10") (pin "89") (pinfunction "VCCINT_89") (pintype "bidirectional"))
      (node (ref "U11") (pin "3") (pinfunction "OUT_3") (pintype "bidirectional"))
    )
    (net (code "2") (name "+2V5") (class "Default")
      (node (ref "C10") (pin "2") (pinfunction "P$2_2") (pintype "bidirectional"))
      (node (ref "C11") (pin "2") (pinfunction "P$2_2") (pintype "bidirectional"))
      (node (ref "C22") (pin "2") (pinfunction "P$2_2") (pintype "bidirectional"))
      (node (ref "C25") (pin "2") (pinfunction "P$2_2") (pintype "bidirectional"))
      (node (ref "C28") (pin "2") (pinfunction "P$2_2") (pintype "bidirectional"))
      (node (ref "C29") (pin "2") (pinfunction "P$2_2") (pintype "bidirectional"))
      (node (ref "C33") (pin "2") (pinfunction "P$2_2") (pintype "bidirectional"))
      (node (ref "C34") (pin "2") (pinfunction "P$2_2") (pintype "bidirectional"))
      (node (ref "C41") (pin "2") (pinfunction "P$2_2") (pintype "bidirectional"))
      (node (ref "C42") (pin "2") (pinfunction "P$2_2") (pintype "bidirectional"))
      (node (ref "C43") (pin "2") (pinfunction "P$2_2") (pintype "bidirectional"))
      (node (ref "C44") (pin "2") (pinfunction "P$2_2") (pintype "bidirectional"))
      (node (ref "C45") (pin "2") (pinfunction "P$2_2") (pintype "bidirectional"))
      (node (ref "C46") (pin "2") (pinfunction "P$2_2") (pintype "bidirectional"))
      (node (ref "C47") (pin "2") (pinfunction "P$2_2") (pintype "bidirectional"))
      (node (ref "C48") (pin "2") (pinfunction "P$2_2") (pintype "bidirectional"))
      (node (ref "C49") (pin "2") (pinfunction "P$2_2") (pintype "bidirectional"))
      (node (ref "C50") (pin "2") (pinfunction "P$2_2") (pintype "bidirectional"))
      (node (ref "C51") (pin "2") (pinfunction "P$2_2") (pintype "bidirectional"))
      (node (ref "C52") (pin "2") (pinfunction "P$2_2") (pintype "bidirectional"))
      (node (ref "C53") (pin "2") (pinfunction "P$2_2") (pintype "bidirectional"))
      (node (ref "C54") (pin "2") (pinfunction "P$2_2") (pintype "bidirectional"))
      (node (ref "C55") (pin "2") (pinfunction "P$2_2") (pintype "bidirectional"))
      (node (ref "C56") (pin "2") (pinfunction "P$2_2") (pintype "bidirectional"))
      (node (ref "C57") (pin "2") (pinfunction "P$2_2") (pintype "bidirectional"))
      (node (ref "C58") (pin "2") (pinfunction "P$2_2") (pintype "bidirectional"))
      (node (ref "C59") (pin "2") (pinfunction "P$2_2") (pintype "bidirectional"))
      (node (ref "C60") (pin "2") (pinfunction "P$2_2") (pintype "bidirectional"))
      (node (ref "C61") (pin "2") (pinfunction "P$2_2") (pintype "bidirectional"))
      (node (ref "C63") (pin "2") (pinfunction "P$2_2") (pintype "bidirectional"))
      (node (ref "C68") (pin "2") (pinfunction "P$2_2") (pintype "bidirectional"))
      (node (ref "C7") (pin "2") (pinfunction "P$2_2") (pintype "bidirectional"))
      (node (ref "C8") (pin "2") (pinfunction "P$2_2") (pintype "bidirectional"))
      (node (ref "C9") (pin "2") (pinfunction "P$2_2") (pintype "bidirectional"))
      (node (ref "D1") (pin "A") (pinfunction "A_A") (pintype "bidirectional"))
      (node (ref "D2") (pin "A") (pinfunction "A_A") (pintype "bidirectional"))
      (node (ref "D4") (pin "A") (pinfunction "A_A") (pintype "bidirectional"))
      (node (ref "J2") (pin "2") (pinfunction "VDD_TARGET_2") (pintype "bidirectional"))
      (node (ref "J4") (pin "2") (pinfunction "VREF_2") (pintype "bidirectional"))
      (node (ref "R1") (pin "P$2") (pinfunction "P$2_P$2") (pintype "bidirectional"))
      (node (ref "R10") (pin "P$2") (pinfunction "P$2_P$2") (pintype "bidirectional"))
      (node (ref "R15") (pin "P$2") (pinfunction "P$2_P$2") (pintype "bidirectional"))
      (node (ref "R16") (pin "P$2") (pinfunction "P$2_P$2") (pintype "bidirectional"))
      (node (ref "R19") (pin "P$2") (pinfunction "P$2_P$2") (pintype "bidirectional"))
      (node (ref "R20") (pin "P$2") (pinfunction "P$2_P$2") (pintype "bidirectional"))
      (node (ref "R21") (pin "P$2") (pinfunction "P$2_P$2") (pintype "bidirectional"))
      (node (ref "R6") (pin "P$2") (pinfunction "P$2_P$2") (pintype "bidirectional"))
      (node (ref "R8") (pin "P$2") (pinfunction "P$2_P$2") (pintype "bidirectional"))
      (node (ref "R9") (pin "P$2") (pinfunction "P$2_P$2") (pintype "bidirectional"))
      (node (ref "U1") (pin "1") (pinfunction "VCCA_1") (pintype "bidirectional"))
      (node (ref "U10") (pin "103") (pinfunction "VCCO_1_103") (pintype "bidirectional"))
      (node (ref "U10") (pin "122") (pinfunction "VCCO_0_122") (pintype "bidirectional"))
      (node (ref "U10") (pin "125") (pinfunction "VCCO_0_125") (pintype "bidirectional"))
      (node (ref "U10") (pin "129") (pinfunction "VCCAUX_129") (pintype "bidirectional"))
      (node (ref "U10") (pin "135") (pinfunction "VCCO_0_135") (pintype "bidirectional"))
      (node (ref "U10") (pin "18") (pinfunction "VCCO_3_18") (pintype "bidirectional"))
      (node (ref "U10") (pin "20") (pinfunction "VCCAUX_20") (pintype "bidirectional"))
      (node (ref "U10") (pin "31") (pinfunction "VCCO_3_31") (pintype "bidirectional"))
      (node (ref "U10") (pin "36") (pinfunction "VCCAUX_36") (pintype "bidirectional"))
      (node (ref "U10") (pin "4") (pinfunction "VCCO_3_4") (pintype "bidirectional"))
      (node (ref "U10") (pin "42") (pinfunction "VCCO_2_42") (pintype "bidirectional"))
      (node (ref "U10") (pin "53") (pinfunction "VCCAUX_53") (pintype "bidirectional"))
      (node (ref "U10") (pin "60") (pinfunction "IO_L13P_M1_2_60") (pintype "bidirectional"))
      (node (ref "U10") (pin "63") (pinfunction "VCCO_2_63") (pintype "bidirectional"))
      (node (ref "U10") (pin "69") (pinfunction "IO_L1N_M0_CMPMISO_2_69") (pintype "bidirectional"))
      (node (ref "U10") (pin "76") (pinfunction "VCCO_1_76") (pintype "bidirectional"))
      (node (ref "U10") (pin "86") (pinfunction "VCCO_1_86") (pintype "bidirectional"))
      (node (ref "U10") (pin "90") (pinfunction "VCCAUX_90") (pintype "bidirectional"))
      (node (ref "U12") (pin "6") (pinfunction "VCCB_6") (pintype "bidirectional"))
      (node (ref "U13") (pin "6") (pinfunction "VCCB_6") (pintype "bidirectional"))
      (node (ref "U15") (pin "2") (pinfunction "OUT_2") (pintype "bidirectional"))
      (node (ref "U17") (pin "1") (pinfunction "VCCA_1") (pintype "bidirectional"))
      (node (ref "U17") (pin "5") (pinfunction "DIR_5") (pintype "bidirectional"))
      (node (ref "U18") (pin "1") (pinfunction "VCCA_1") (pintype "bidirectional"))
      (node (ref "U18") (pin "5") (pinfunction "DIR_5") (pintype "bidirectional"))
      (node (ref "U2") (pin "1") (pinfunction "VCCA_1") (pintype "bidirectional"))
      (node (ref "U3") (pin "1") (pinfunction "VCCA_1") (pintype "bidirectional"))
      (node (ref "U4") (pin "1") (pinfunction "VCCA_1") (pintype "bidirectional"))
      (node (ref "U4") (pin "2") (pinfunction "DIR_2") (pintype "bidirectional"))
      (node (ref "U5") (pin "1") (pinfunction "VCCA_1") (pintype "bidirectional"))
      (node (ref "U5") (pin "2") (pinfunction "DIR_2") (pintype "bidirectional"))
      (node (ref "U7") (pin "28") (pinfunction "VDD_28") (pintype "bidirectional"))
      (node (ref "U7") (pin "7") (pinfunction "VDD_7") (pintype "bidirectional"))
      (node (ref "U8") (pin "3") (pinfunction "/W_3") (pintype "bidirectional"))
      (node (ref "U8") (pin "8") (pinfunction "VCC_8") (pintype "bidirectional"))
      (node (ref "U9") (pin "4") (pinfunction "VCCIO_4") (pintype "bidirectional"))
    )
    (net (code "3") (name "+5V") (class "Default")
      (node (ref "C12") (pin "2") (pinfunction "P$2_2") (pintype "bidirectional"))
      (node (ref "C13") (pin "2") (pinfunction "P$2_2") (pintype "bidirectional"))
      (node (ref "C14") (pin "2") (pinfunction "P$2_2") (pintype "bidirectional"))
      (node (ref "C15") (pin "2") (pinfunction "P$2_2") (pintype "bidirectional"))
      (node (ref "C16") (pin "2") (pinfunction "P$2_2") (pintype "bidirectional"))
      (node (ref "C18") (pin "2") (pinfunction "P$2_2") (pintype "bidirectional"))
      (node (ref "C19") (pin "2") (pinfunction "P$2_2") (pintype "bidirectional"))
      (node (ref "C20") (pin "2") (pinfunction "P$2_2") (pintype "bidirectional"))
      (node (ref "C23") (pin "2") (pinfunction "P$2_2") (pintype "bidirectional"))
      (node (ref "C26") (pin "2") (pinfunction "P$2_2") (pintype "bidirectional"))
      (node (ref "C3") (pin "2") (pinfunction "P$2_2") (pintype "bidirectional"))
      (node (ref "C30") (pin "2") (pinfunction "P$2_2") (pintype "bidirectional"))
      (node (ref "C31") (pin "2") (pinfunction "P$2_2") (pintype "bidirectional"))
      (node (ref "C4") (pin "2") (pinfunction "P$2_2") (pintype "bidirectional"))
      (node (ref "C5") (pin "2") (pinfunction "P$2_2") (pintype "bidirectional"))
      (node (ref "C6") (pin "2") (pinfunction "P$2_2") (pintype "bidirectional"))
      (node (ref "C62") (pin "2") (pinfunction "P$2_2") (pintype "bidirectional"))
      (node (ref "C69") (pin "2") (pinfunction "P$2_2") (pintype "bidirectional"))
      (node (ref "C71") (pin "2") (pinfunction "P$2_2") (pintype "bidirectional"))
      (node (ref "J1") (pin "40") (pinfunction "40_40") (pintype "bidirectional"))
      (node (ref "J5") (pin "8") (pinfunction "8_8") (pintype "bidirectional"))
      (node (ref "R18") (pin "P$2") (pinfunction "P$2_P$2") (pintype "bidirectional"))
      (node (ref "R22") (pin "P$2") (pinfunction "P$2_P$2") (pintype "bidirectional"))
      (node (ref "R29") (pin "P$2") (pinfunction "P$2_P$2") (pintype "bidirectional"))
      (node (ref "R33") (pin "P$2") (pinfunction "P$2_P$2") (pintype "bidirectional"))
      (node (ref "R36") (pin "P$2") (pinfunction "P$2_P$2") (pintype "bidirectional"))
      (node (ref "R39") (pin "P$2") (pinfunction "P$2_P$2") (pintype "bidirectional"))
      (node (ref "R42") (pin "P$2") (pinfunction "P$2_P$2") (pintype "bidirectional"))
      (node (ref "R45") (pin "P$2") (pinfunction "P$2_P$2") (pintype "bidirectional"))
      (node (ref "R48") (pin "P$2") (pinfunction "P$2_P$2") (pintype "bidirectional"))
      (node (ref "U1") (pin "23") (pinfunction "VCCB_23") (pintype "bidirectional"))
      (node (ref "U1") (pin "24") (pinfunction "VCCB_24") (pintype "bidirectional"))
      (node (ref "U11") (pin "1") (pinfunction "IN_1") (pintype "bidirectional"))
      (node (ref "U12") (pin "1") (pinfunction "VCCA_1") (pintype "bidirectional"))
      (node (ref "U12") (pin "5") (pinfunction "DIR_5") (pintype "bidirectional"))
      (node (ref "U13") (pin "1") (pinfunction "VCCA_1") (pintype "bidirectional"))
      (node (ref "U15") (pin "3") (pinfunction "IN_3") (pintype "bidirectional"))
      (node (ref "U17") (pin "6") (pinfunction "VCCB_6") (pintype "bidirectional"))
      (node (ref "U18") (pin "6") (pinfunction "VCCB_6") (pintype "bidirectional"))
      (node (ref "U19") (pin "1") (pinfunction "VCC_SYNC_1") (pintype "bidirectional"))
      (node (ref "U19") (pin "2") (pinfunction "VCC_VIDEO_2") (pintype "bidirectional"))
      (node (ref "U2") (pin "23") (pinfunction "VCCB_23") (pintype "bidirectional"))
      (node (ref "U2") (pin "24") (pinfunction "VCCB_24") (pintype "bidirectional"))
      (node (ref "U3") (pin "23") (pinfunction "VCCB_23") (pintype "bidirectional"))
      (node (ref "U3") (pin "24") (pinfunction "VCCB_24") (pintype "bidirectional"))
      (node (ref "U4") (pin "23") (pinfunction "VCCB_23") (pintype "bidirectional"))
      (node (ref "U4") (pin "24") (pinfunction "VCCB_24") (pintype "bidirectional"))
      (node (ref "U5") (pin "23") (pinfunction "VCCB_23") (pintype "bidirectional"))
      (node (ref "U5") (pin "24") (pinfunction "VCCB_24") (pintype "bidirectional"))
      (node (ref "U6") (pin "13") (pinfunction "VAA_13") (pintype "bidirectional"))
      (node (ref "U6") (pin "29") (pinfunction "VAA_29") (pintype "bidirectional"))
      (node (ref "U6") (pin "30") (pinfunction "VAA_30") (pintype "bidirectional"))
      (node (ref "U6") (pin "38") (pinfunction "/PSAVE_38") (pintype "bidirectional"))
      (node (ref "U9") (pin "20") (pinfunction "VCC_20") (pintype "bidirectional"))
      (node (ref "Y1") (pin "4") (pinfunction "VCC_4") (pintype "bidirectional"))
    )
    (net (code "4") (name "A0") (class "Default")
      (node (ref "J1") (pin "12") (pinfunction "12_12") (pintype "bidirectional"))
      (node (ref "U2") (pin "18") (pinfunction "B4_18") (pintype "bidirectional"))
    )
    (net (code "5") (name "A1") (class "Default")
      (node (ref "J1") (pin "11") (pinfunction "11_11") (pintype "bidirectional"))
      (node (ref "U2") (pin "19") (pinfunction "B3_19") (pintype "bidirectional"))
    )
    (net (code "6") (name "A2") (class "Default")
      (node (ref "J1") (pin "10") (pinfunction "10_10") (pintype "bidirectional"))
      (node (ref "U2") (pin "20") (pinfunction "B2_20") (pintype "bidirectional"))
    )
    (net (code "7") (name "A8") (class "Default")
      (node (ref "J1") (pin "30") (pinfunction "30_30") (pintype "bidirectional"))
      (node (ref "U5") (pin "16") (pinfunction "B6_16") (pintype "bidirectional"))
    )
    (net (code "8") (name "A9") (class "Default")
      (node (ref "J1") (pin "29") (pinfunction "29_29") (pintype "bidirectional"))
      (node (ref "U5") (pin "17") (pinfunction "B5_17") (pintype "bidirectional"))
    )
    (net (code "9") (name "A10") (class "Default")
      (node (ref "J1") (pin "28") (pinfunction "28_28") (pintype "bidirectional"))
      (node (ref "U5") (pin "18") (pinfunction "B4_18") (pintype "bidirectional"))
    )
    (net (code "10") (name "A11") (class "Default")
      (node (ref "J1") (pin "27") (pinfunction "27_27") (pintype "bidirectional"))
      (node (ref "U5") (pin "19") (pinfunction "B3_19") (pintype "bidirectional"))
    )
    (net (code "11") (name "A12") (class "Default")
      (node (ref "J1") (pin "26") (pinfunction "26_26") (pintype "bidirectional"))
      (node (ref "U5") (pin "20") (pinfunction "B2_20") (pintype "bidirectional"))
    )
    (net (code "12") (name "A13") (class "Default")
      (node (ref "J1") (pin "25") (pinfunction "25_25") (pintype "bidirectional"))
      (node (ref "U5") (pin "21") (pinfunction "B1_21") (pintype "bidirectional"))
    )
    (net (code "13") (name "AD0") (class "Default")
      (node (ref "J1") (pin "38") (pinfunction "38_38") (pintype "bidirectional"))
      (node (ref "U1") (pin "21") (pinfunction "B1_21") (pintype "bidirectional"))
    )
    (net (code "14") (name "AD1") (class "Default")
      (node (ref "J1") (pin "37") (pinfunction "37_37") (pintype "bidirectional"))
      (node (ref "U1") (pin "20") (pinfunction "B2_20") (pintype "bidirectional"))
    )
    (net (code "15") (name "AD2") (class "Default")
      (node (ref "J1") (pin "36") (pinfunction "36_36") (pintype "bidirectional"))
      (node (ref "U1") (pin "19") (pinfunction "B3_19") (pintype "bidirectional"))
    )
    (net (code "16") (name "AD3") (class "Default")
      (node (ref "J1") (pin "35") (pinfunction "35_35") (pintype "bidirectional"))
      (node (ref "U1") (pin "18") (pinfunction "B4_18") (pintype "bidirectional"))
    )
    (net (code "17") (name "AD4") (class "Default")
      (node (ref "J1") (pin "34") (pinfunction "34_34") (pintype "bidirectional"))
      (node (ref "U1") (pin "17") (pinfunction "B5_17") (pintype "bidirectional"))
    )
    (net (code "18") (name "AD5") (class "Default")
      (node (ref "J1") (pin "33") (pinfunction "33_33") (pintype "bidirectional"))
      (node (ref "U1") (pin "16") (pinfunction "B6_16") (pintype "bidirectional"))
    )
    (net (code "19") (name "AD6") (class "Default")
      (node (ref "J1") (pin "32") (pinfunction "32_32") (pintype "bidirectional"))
      (node (ref "U1") (pin "15") (pinfunction "B7_15") (pintype "bidirectional"))
    )
    (net (code "20") (name "AD7") (class "Default")
      (node (ref "J1") (pin "31") (pinfunction "31_31") (pintype "bidirectional"))
      (node (ref "U1") (pin "14") (pinfunction "B8_14") (pintype "bidirectional"))
    )
    (net (code "21") (name "ALE") (class "Default")
      (node (ref "J1") (pin "39") (pinfunction "39_39") (pintype "bidirectional"))
      (node (ref "U5") (pin "15") (pinfunction "B7_15") (pintype "bidirectional"))
    )
    (net (code "22") (name "CLK") (class "Default")
      (node (ref "J1") (pin "18") (pinfunction "18_18") (pintype "bidirectional"))
      (node (ref "U2") (pin "15") (pinfunction "B7_15") (pintype "bidirectional"))
    )
    (net (code "23") (name "CSYNC") (class "Default")
      (node (ref "U10") (pin "41") (pinfunction "IO_L64P_D8_2_41") (pintype "bidirectional"))
      (node (ref "U17") (pin "3") (pinfunction "A_3") (pintype "bidirectional"))
    )
    (net (code "24") (name "D0") (class "Default")
      (node (ref "J1") (pin "2") (pinfunction "2_2") (pintype "bidirectional"))
      (node (ref "R28") (pin "P$1") (pinfunction "P$1_P$1") (pintype "bidirectional"))
      (node (ref "U3") (pin "21") (pinfunction "B1_21") (pintype "bidirectional"))
    )
    (net (code "25") (name "D1") (class "Default")
      (node (ref "J1") (pin "3") (pinfunction "3_3") (pintype "bidirectional"))
      (node (ref "R17") (pin "P$1") (pinfunction "P$1_P$1") (pintype "bidirectional"))
      (node (ref "U3") (pin "20") (pinfunction "B2_20") (pintype "bidirectional"))
    )
    (net (code "26") (name "D2") (class "Default")
      (node (ref "J1") (pin "4") (pinfunction "4_4") (pintype "bidirectional"))
      (node (ref "R32") (pin "P$1") (pinfunction "P$1_P$1") (pintype "bidirectional"))
      (node (ref "U3") (pin "19") (pinfunction "B3_19") (pintype "bidirectional"))
    )
    (net (code "27") (name "D3") (class "Default")
      (node (ref "J1") (pin "5") (pinfunction "5_5") (pintype "bidirectional"))
      (node (ref "R35") (pin "P$1") (pinfunction "P$1_P$1") (pintype "bidirectional"))
      (node (ref "U3") (pin "18") (pinfunction "B4_18") (pintype "bidirectional"))
    )
    (net (code "28") (name "D4") (class "Default")
      (node (ref "J1") (pin "6") (pinfunction "6_6") (pintype "bidirectional"))
      (node (ref "R38") (pin "P$1") (pinfunction "P$1_P$1") (pintype "bidirectional"))
      (node (ref "U3") (pin "17") (pinfunction "B5_17") (pintype "bidirectional"))
    )
    (net (code "29") (name "D5") (class "Default")
      (node (ref "J1") (pin "7") (pinfunction "7_7") (pintype "bidirectional"))
      (node (ref "R41") (pin "P$1") (pinfunction "P$1_P$1") (pintype "bidirectional"))
      (node (ref "U3") (pin "16") (pinfunction "B6_16") (pintype "bidirectional"))
    )
    (net (code "30") (name "D6") (class "Default")
      (node (ref "J1") (pin "8") (pinfunction "8_8") (pintype "bidirectional"))
      (node (ref "R44") (pin "P$1") (pinfunction "P$1_P$1") (pintype "bidirectional"))
      (node (ref "U3") (pin "15") (pinfunction "B7_15") (pintype "bidirectional"))
    )
    (net (code "31") (name "D7") (class "Default")
      (node (ref "J1") (pin "9") (pinfunction "9_9") (pintype "bidirectional"))
      (node (ref "R47") (pin "P$1") (pinfunction "P$1_P$1") (pintype "bidirectional"))
      (node (ref "U3") (pin "14") (pinfunction "B8_14") (pintype "bidirectional"))
    )
    (net (code "32") (name "DGND") (class "Default")
      (node (ref "C1") (pin "2") (pinfunction "P$2_2") (pintype "bidirectional"))
      (node (ref "C10") (pin "1") (pinfunction "P$1_1") (pintype "bidirectional"))
      (node (ref "C11") (pin "1") (pinfunction "P$1_1") (pintype "bidirectional"))
      (node (ref "C12") (pin "1") (pinfunction "P$1_1") (pintype "bidirectional"))
      (node (ref "C13") (pin "1") (pinfunction "P$1_1") (pintype "bidirectional"))
      (node (ref "C14") (pin "1") (pinfunction "P$1_1") (pintype "bidirectional"))
      (node (ref "C15") (pin "1") (pinfunction "P$1_1") (pintype "bidirectional"))
      (node (ref "C16") (pin "1") (pinfunction "P$1_1") (pintype "bidirectional"))
      (node (ref "C17") (pin "1") (pinfunction "P$1_1") (pintype "bidirectional"))
      (node (ref "C18") (pin "1") (pinfunction "P$1_1") (pintype "bidirectional"))
      (node (ref "C19") (pin "1") (pinfunction "P$1_1") (pintype "bidirectional"))
      (node (ref "C2") (pin "1") (pinfunction "P$1_1") (pintype "bidirectional"))
      (node (ref "C20") (pin "1") (pinfunction "P$1_1") (pintype "bidirectional"))
      (node (ref "C21") (pin "1") (pinfunction "P$1_1") (pintype "bidirectional"))
      (node (ref "C22") (pin "1") (pinfunction "P$1_1") (pintype "bidirectional"))
      (node (ref "C24") (pin "1") (pinfunction "P$1_1") (pintype "bidirectional"))
      (node (ref "C25") (pin "1") (pinfunction "P$1_1") (pintype "bidirectional"))
      (node (ref "C26") (pin "1") (pinfunction "P$1_1") (pintype "bidirectional"))
      (node (ref "C28") (pin "1") (pinfunction "P$1_1") (pintype "bidirectional"))
      (node (ref "C29") (pin "1") (pinfunction "P$1_1") (pintype "bidirectional"))
      (node (ref "C3") (pin "1") (pinfunction "P$1_1") (pintype "bidirectional"))
      (node (ref "C30") (pin "1") (pinfunction "P$1_1") (pintype "bidirectional"))
      (node (ref "C31") (pin "1") (pinfunction "P$1_1") (pintype "bidirectional"))
      (node (ref "C33") (pin "1") (pinfunction "P$1_1") (pintype "bidirectional"))
      (node (ref "C34") (pin "1") (pinfunction "P$1_1") (pintype "bidirectional"))
      (node (ref "C37") (pin "1") (pinfunction "P$1_1") (pintype "bidirectional"))
      (node (ref "C38") (pin "1") (pinfunction "P$1_1") (pintype "bidirectional"))
      (node (ref "C39") (pin "1") (pinfunction "P$1_1") (pintype "bidirectional"))
      (node (ref "C4") (pin "1") (pinfunction "P$1_1") (pintype "bidirectional"))
      (node (ref "C40") (pin "1") (pinfunction "P$1_1") (pintype "bidirectional"))
      (node (ref "C41") (pin "1") (pinfunction "P$1_1") (pintype "bidirectional"))
      (node (ref "C42") (pin "1") (pinfunction "P$1_1") (pintype "bidirectional"))
      (node (ref "C43") (pin "1") (pinfunction "P$1_1") (pintype "bidirectional"))
      (node (ref "C44") (pin "1") (pinfunction "P$1_1") (pintype "bidirectional"))
      (node (ref "C45") (pin "1") (pinfunction "P$1_1") (pintype "bidirectional"))
      (node (ref "C46") (pin "1") (pinfunction "P$1_1") (pintype "bidirectional"))
      (node (ref "C47") (pin "1") (pinfunction "P$1_1") (pintype "bidirectional"))
      (node (ref "C48") (pin "1") (pinfunction "P$1_1") (pintype "bidirectional"))
      (node (ref "C49") (pin "1") (pinfunction "P$1_1") (pintype "bidirectional"))
      (node (ref "C5") (pin "1") (pinfunction "P$1_1") (pintype "bidirectional"))
      (node (ref "C50") (pin "1") (pinfunction "P$1_1") (pintype "bidirectional"))
      (node (ref "C51") (pin "1") (pinfunction "P$1_1") (pintype "bidirectional"))
      (node (ref "C52") (pin "1") (pinfunction "P$1_1") (pintype "bidirectional"))
      (node (ref "C53") (pin "1") (pinfunction "P$1_1") (pintype "bidirectional"))
      (node (ref "C54") (pin "1") (pinfunction "P$1_1") (pintype "bidirectional"))
      (node (ref "C55") (pin "1") (pinfunction "P$1_1") (pintype "bidirectional"))
      (node (ref "C56") (pin "1") (pinfunction "P$1_1") (pintype "bidirectional"))
      (node (ref "C57") (pin "1") (pinfunction "P$1_1") (pintype "bidirectional"))
      (node (ref "C58") (pin "1") (pinfunction "P$1_1") (pintype "bidirectional"))
      (node (ref "C59") (pin "1") (pinfunction "P$1_1") (pintype "bidirectional"))
      (node (ref "C6") (pin "1") (pinfunction "P$1_1") (pintype "bidirectional"))
      (node (ref "C60") (pin "1") (pinfunction "P$1_1") (pintype "bidirectional"))
      (node (ref "C61") (pin "1") (pinfunction "P$1_1") (pintype "bidirectional"))
      (node (ref "C62") (pin "1") (pinfunction "P$1_1") (pintype "bidirectional"))
      (node (ref "C63") (pin "1") (pinfunction "P$1_1") (pintype "bidirectional"))
      (node (ref "C68") (pin "1") (pinfunction "P$1_1") (pintype "bidirectional"))
      (node (ref "C69") (pin "1") (pinfunction "P$1_1") (pintype "bidirectional"))
      (node (ref "C7") (pin "1") (pinfunction "P$1_1") (pintype "bidirectional"))
      (node (ref "C70") (pin "1") (pinfunction "P$1_1") (pintype "bidirectional"))
      (node (ref "C71") (pin "1") (pinfunction "P$1_1") (pintype "bidirectional"))
      (node (ref "C8") (pin "1") (pinfunction "P$1_1") (pintype "bidirectional"))
      (node (ref "C9") (pin "1") (pinfunction "P$1_1") (pintype "bidirectional"))
      (node (ref "D3") (pin "2") (pinfunction "V-_2") (pintype "bidirectional"))
      (node (ref "J1") (pin "20") (pinfunction "20_20") (pintype "bidirectional"))
      (node (ref "J2") (pin "3") (pinfunction "VSS_3") (pintype "bidirectional"))
      (node (ref "J3") (pin "5") (pinfunction "GND_5") (pintype "bidirectional"))
      (node (ref "J4") (pin "11") (pinfunction "GND_11") (pintype "bidirectional"))
      (node (ref "J4") (pin "3") (pinfunction "GND_3") (pintype "bidirectional"))
      (node (ref "J4") (pin "5") (pinfunction "GND_5") (pintype "bidirectional"))
      (node (ref "J4") (pin "7") (pinfunction "GND_7") (pintype "bidirectional"))
      (node (ref "J4") (pin "9") (pinfunction "GND_9") (pintype "bidirectional"))
      (node (ref "J5") (pin "2") (pinfunction "2_2") (pintype "bidirectional"))
      (node (ref "J5") (pin "4") (pinfunction "4_4") (pintype "bidirectional"))
      (node (ref "J5") (pin "6") (pinfunction "6_6") (pintype "bidirectional"))
      (node (ref "J6") (pin "10") (pinfunction "10_10") (pintype "bidirectional"))
      (node (ref "J6") (pin "12") (pinfunction "12_12") (pintype "bidirectional"))
      (node (ref "J6") (pin "2") (pinfunction "2_2") (pintype "bidirectional"))
      (node (ref "J6") (pin "4") (pinfunction "4_4") (pintype "bidirectional"))
      (node (ref "J6") (pin "6") (pinfunction "6_6") (pintype "bidirectional"))
      (node (ref "J6") (pin "8") (pinfunction "8_8") (pintype "bidirectional"))
      (node (ref "R11") (pin "P$1") (pinfunction "P$1_P$1") (pintype "bidirectional"))
      (node (ref "R12") (pin "P$1") (pinfunction "P$1_P$1") (pintype "bidirectional"))
      (node (ref "R13") (pin "P$1") (pinfunction "P$1_P$1") (pintype "bidirectional"))
      (node (ref "R14") (pin "P$1") (pinfunction "P$1_P$1") (pintype "bidirectional"))
      (node (ref "R23") (pin "P$1") (pinfunction "P$1_P$1") (pintype "bidirectional"))
      (node (ref "R24") (pin "P$1") (pinfunction "P$1_P$1") (pintype "bidirectional"))
      (node (ref "R27") (pin "P$1") (pinfunction "P$1_P$1") (pintype "bidirectional"))
      (node (ref "R30") (pin "P$1") (pinfunction "P$1_P$1") (pintype "bidirectional"))
      (node (ref "R31") (pin "P$1") (pinfunction "P$1_P$1") (pintype "bidirectional"))
      (node (ref "R34") (pin "P$1") (pinfunction "P$1_P$1") (pintype "bidirectional"))
      (node (ref "R37") (pin "P$1") (pinfunction "P$1_P$1") (pintype "bidirectional"))
      (node (ref "R4") (pin "P$1") (pinfunction "P$1_P$1") (pintype "bidirectional"))
      (node (ref "R40") (pin "P$1") (pinfunction "P$1_P$1") (pintype "bidirectional"))
      (node (ref "R43") (pin "P$1") (pinfunction "P$1_P$1") (pintype "bidirectional"))
      (node (ref "R46") (pin "P$1") (pinfunction "P$1_P$1") (pintype "bidirectional"))
      (node (ref "R49") (pin "P$1") (pinfunction "P$1_P$1") (pintype "bidirectional"))
      (node (ref "R7") (pin "P$1") (pinfunction "P$1_P$1") (pintype "bidirectional"))
      (node (ref "U1") (pin "11") (pinfunction "GND_11") (pintype "bidirectional"))
      (node (ref "U1") (pin "12") (pinfunction "GND_12") (pintype "bidirectional"))
      (node (ref "U1") (pin "13") (pinfunction "GND_13") (pintype "bidirectional"))
      (node (ref "U10") (pin "108") (pinfunction "GND_108") (pintype "bidirectional"))
      (node (ref "U10") (pin "113") (pinfunction "GND_113") (pintype "bidirectional"))
      (node (ref "U10") (pin "13") (pinfunction "GND_13") (pintype "bidirectional"))
      (node (ref "U10") (pin "130") (pinfunction "GND_130") (pintype "bidirectional"))
      (node (ref "U10") (pin "136") (pinfunction "GND_136") (pintype "bidirectional"))
      (node (ref "U10") (pin "144") (pinfunction "IO_L1P_HSWAPEN_0_144") (pintype "bidirectional"))
      (node (ref "U10") (pin "25") (pinfunction "GND_25") (pintype "bidirectional"))
      (node (ref "U10") (pin "3") (pinfunction "GND_3") (pintype "bidirectional"))
      (node (ref "U10") (pin "49") (pinfunction "GND_49") (pintype "bidirectional"))
      (node (ref "U10") (pin "54") (pinfunction "GND_54") (pintype "bidirectional"))
      (node (ref "U10") (pin "68") (pinfunction "GND_68") (pintype "bidirectional"))
      (node (ref "U10") (pin "73") (pinfunction "SUSPEND_73") (pintype "bidirectional"))
      (node (ref "U10") (pin "77") (pinfunction "GND_77") (pintype "bidirectional"))
      (node (ref "U10") (pin "91") (pinfunction "GND_91") (pintype "bidirectional"))
      (node (ref "U10") (pin "96") (pinfunction "GND_96") (pintype "bidirectional"))
      (node (ref "U11") (pin "2") (pinfunction "GND_2") (pintype "bidirectional"))
      (node (ref "U11") (pin "4") (pinfunction "GND_4") (pintype "bidirectional"))
      (node (ref "U12") (pin "2") (pinfunction "GND_2") (pintype "bidirectional"))
      (node (ref "U13") (pin "2") (pinfunction "GND_2") (pintype "bidirectional"))
      (node (ref "U15") (pin "1") (pinfunction "GND_1") (pintype "bidirectional"))
      (node (ref "U17") (pin "2") (pinfunction "GND_2") (pintype "bidirectional"))
      (node (ref "U18") (pin "2") (pinfunction "GND_2") (pintype "bidirectional"))
      (node (ref "U19") (pin "10") (pinfunction "DDC_IN1_10") (pintype "bidirectional"))
      (node (ref "U19") (pin "11") (pinfunction "DDC_IN2_11") (pintype "bidirectional"))
      (node (ref "U19") (pin "6") (pinfunction "GND_6") (pintype "bidirectional"))
      (node (ref "U2") (pin "11") (pinfunction "GND_11") (pintype "bidirectional"))
      (node (ref "U2") (pin "12") (pinfunction "GND_12") (pintype "bidirectional"))
      (node (ref "U2") (pin "13") (pinfunction "GND_13") (pintype "bidirectional"))
      (node (ref "U2") (pin "14") (pinfunction "B8_14") (pintype "bidirectional"))
      (node (ref "U2") (pin "2") (pinfunction "DIR_2") (pintype "bidirectional"))
      (node (ref "U3") (pin "11") (pinfunction "GND_11") (pintype "bidirectional"))
      (node (ref "U3") (pin "12") (pinfunction "GND_12") (pintype "bidirectional"))
      (node (ref "U3") (pin "13") (pinfunction "GND_13") (pintype "bidirectional"))
      (node (ref "U4") (pin "11") (pinfunction "GND_11") (pintype "bidirectional"))
      (node (ref "U4") (pin "12") (pinfunction "GND_12") (pintype "bidirectional"))
      (node (ref "U4") (pin "13") (pinfunction "GND_13") (pintype "bidirectional"))
      (node (ref "U4") (pin "4") (pinfunction "A2_4") (pintype "bidirectional"))
      (node (ref "U4") (pin "7") (pinfunction "A5_7") (pintype "bidirectional"))
      (node (ref "U4") (pin "8") (pinfunction "A6_8") (pintype "bidirectional"))
      (node (ref "U4") (pin "9") (pinfunction "A7_9") (pintype "bidirectional"))
      (node (ref "U5") (pin "10") (pinfunction "A8_10") (pintype "bidirectional"))
      (node (ref "U5") (pin "11") (pinfunction "GND_11") (pintype "bidirectional"))
      (node (ref "U5") (pin "12") (pinfunction "GND_12") (pintype "bidirectional"))
      (node (ref "U5") (pin "13") (pinfunction "GND_13") (pintype "bidirectional"))
      (node (ref "U6") (pin "1") (pinfunction "GND_1") (pintype "bidirectional"))
      (node (ref "U6") (pin "14") (pinfunction "GND_14") (pintype "bidirectional"))
      (node (ref "U6") (pin "15") (pinfunction "GND_15") (pintype "bidirectional"))
      (node (ref "U6") (pin "2") (pinfunction "GND_2") (pintype "bidirectional"))
      (node (ref "U6") (pin "25") (pinfunction "GND_25") (pintype "bidirectional"))
      (node (ref "U6") (pin "26") (pinfunction "GND_26") (pintype "bidirectional"))
      (node (ref "U6") (pin "27") (pinfunction "/IOB_27") (pintype "bidirectional"))
      (node (ref "U6") (pin "31") (pinfunction "/IOG_31") (pintype "bidirectional"))
      (node (ref "U6") (pin "33") (pinfunction "/IOR_33") (pintype "bidirectional"))
      (node (ref "U6") (pin "39") (pinfunction "GND_39") (pintype "bidirectional"))
      (node (ref "U6") (pin "40") (pinfunction "GND_40") (pintype "bidirectional"))
      (node (ref "U7") (pin "29") (pinfunction "VSS_29") (pintype "bidirectional"))
      (node (ref "U7") (pin "6") (pinfunction "VSS_6") (pintype "bidirectional"))
      (node (ref "U8") (pin "4") (pinfunction "VSS_4") (pintype "bidirectional"))
      (node (ref "U9") (pin "18") (pinfunction "GND_18") (pintype "bidirectional"))
      (node (ref "U9") (pin "21") (pinfunction "GND_21") (pintype "bidirectional"))
      (node (ref "U9") (pin "25") (pinfunction "AGND_25") (pintype "bidirectional"))
      (node (ref "U9") (pin "26") (pinfunction "TEST_26") (pintype "bidirectional"))
      (node (ref "U9") (pin "7") (pinfunction "GND_7") (pintype "bidirectional"))
      (node (ref "Y1") (pin "2") (pinfunction "GND_2") (pintype "bidirectional"))
    )
    (net (code "33") (name "FLASH_CLK") (class "Default")
      (node (ref "U7") (pin "37") (pinfunction "RC3_37") (pintype "bidirectional"))
      (node (ref "U8") (pin "6") (pinfunction "C_6") (pintype "bidirectional"))
    )
    (net (code "34") (name "FLASH_CS") (class "Default")
      (node (ref "U7") (pin "32") (pinfunction "RC0_32") (pintype "bidirectional"))
      (node (ref "U8") (pin "1") (pinfunction "/S_1") (pintype "bidirectional"))
    )
    (net (code "35") (name "FLASH_HOLD") (class "Default")
      (node (ref "U7") (pin "35") (pinfunction "RC1_35") (pintype "bidirectional"))
      (node (ref "U8") (pin "7") (pinfunction "/HOLD_7") (pintype "bidirectional"))
    )
    (net (code "36") (name "FLASH_SDI") (class "Default")
      (node (ref "U7") (pin "43") (pinfunction "RC5_43") (pintype "bidirectional"))
      (node (ref "U8") (pin "5") (pinfunction "D_5") (pintype "bidirectional"))
    )
    (net (code "37") (name "FLASH_SDO") (class "Default")
      (node (ref "U7") (pin "42") (pinfunction "RC4_42") (pintype "bidirectional"))
      (node (ref "U8") (pin "2") (pinfunction "Q_2") (pintype "bidirectional"))
    )
    (net (code "38") (name "FPGA_CCLK") (class "Default")
      (node (ref "R7") (pin "P$2") (pinfunction "P$2_P$2") (pintype "bidirectional"))
      (node (ref "U10") (pin "70") (pinfunction "IO_L1P_CCLK_2_70") (pintype "bidirectional"))
      (node (ref "U7") (pin "38") (pinfunction "RD0_38") (pintype "bidirectional"))
    )
    (net (code "39") (name "FPGA_DIN") (class "Default")
      (node (ref "U10") (pin "65") (pinfunction "IO_L3P_D0_DIN_MISO_MISO1_2_65") (pintype "bidirectional"))
      (node (ref "U7") (pin "2") (pinfunction "RD4_2") (pintype "bidirectional"))
    )
    (net (code "40") (name "FPGA_DONE") (class "Default")
      (node (ref "R8") (pin "P$1") (pinfunction "P$1_P$1") (pintype "bidirectional"))
      (node (ref "U10") (pin "71") (pinfunction "DONE_2_71") (pintype "bidirectional"))
      (node (ref "U7") (pin "41") (pinfunction "RD3_41") (pintype "bidirectional"))
    )
    (net (code "41") (name "FPGA_INIT_B") (class "Default")
      (node (ref "R9") (pin "P$1") (pinfunction "P$1_P$1") (pintype "bidirectional"))
      (node (ref "U10") (pin "39") (pinfunction "IO_L65P_INIT_B_2_39") (pintype "bidirectional"))
      (node (ref "U7") (pin "36") (pinfunction "RC2_36") (pintype "bidirectional"))
    )
    (net (code "42") (name "FPGA_PROGRAM_B") (class "Default")
      (node (ref "R10") (pin "P$1") (pinfunction "P$1_P$1") (pintype "bidirectional"))
      (node (ref "U10") (pin "37") (pinfunction "PROGRAM_B_2_37") (pintype "bidirectional"))
      (node (ref "U7") (pin "40") (pinfunction "RD2_40") (pintype "bidirectional"))
    )
    (net (code "43") (name "JMP1") (class "Default")
      (node (ref "J6") (pin "1") (pinfunction "1_1") (pintype "bidirectional"))
      (node (ref "R21") (pin "P$1") (pinfunction "P$1_P$1") (pintype "bidirectional"))
      (node (ref "U10") (pin "118") (pinfunction "IO_L63N_SCP6_0_118") (pintype "bidirectional"))
    )
    (net (code "44") (name "JMP2") (class "Default")
      (node (ref "J6") (pin "3") (pinfunction "3_3") (pintype "bidirectional"))
      (node (ref "R20") (pin "P$1") (pinfunction "P$1_P$1") (pintype "bidirectional"))
      (node (ref "U10") (pin "117") (pinfunction "IO_L64P_SCP5_0_117") (pintype "bidirectional"))
    )
    (net (code "45") (name "JMP3") (class "Default")
      (node (ref "J6") (pin "5") (pinfunction "5_5") (pintype "bidirectional"))
      (node (ref "R19") (pin "P$1") (pinfunction "P$1_P$1") (pintype "bidirectional"))
      (node (ref "U10") (pin "116") (pinfunction "IO_L64N_SCP4_0_116") (pintype "bidirectional"))
    )
    (net (code "46") (name "JMP4") (class "Default")
      (node (ref "J6") (pin "7") (pinfunction "7_7") (pintype "bidirectional"))
      (node (ref "R6") (pin "P$1") (pinfunction "P$1_P$1") (pintype "bidirectional"))
      (node (ref "U10") (pin "115") (pinfunction "IO_L65P_SCP3_0_115") (pintype "bidirectional"))
    )
    (net (code "47") (name "JMP5") (class "Default")
      (node (ref "J6") (pin "9") (pinfunction "9_9") (pintype "bidirectional"))
      (node (ref "R15") (pin "P$1") (pinfunction "P$1_P$1") (pintype "bidirectional"))
      (node (ref "U10") (pin "114") (pinfunction "IO_L65N_SCP2_0_114") (pintype "bidirectional"))
    )
    (net (code "48") (name "JMP6") (class "Default")
      (node (ref "J6") (pin "11") (pinfunction "11_11") (pintype "bidirectional"))
      (node (ref "R16") (pin "P$1") (pinfunction "P$1_P$1") (pintype "bidirectional"))
      (node (ref "U10") (pin "112") (pinfunction "IO_L66P_SCP1_0_112") (pintype "bidirectional"))
    )
    (net (code "49") (name "Net-(C1-P$1)") (class "Default")
      (node (ref "C1") (pin "1") (pinfunction "P$1_1") (pintype "bidirectional"))
      (node (ref "U9") (pin "17") (pinfunction "3V3OUT_17") (pintype "bidirectional"))
    )
    (net (code "50") (name "Net-(C2-P$2)") (class "Default")
      (node (ref "C2") (pin "2") (pinfunction "P$2_2") (pintype "bidirectional"))
      (node (ref "J3") (pin "1") (pinfunction "VCC_1") (pintype "bidirectional"))
      (node (ref "R5") (pin "P$2") (pinfunction "P$2_P$2") (pintype "bidirectional"))
    )
    (net (code "51") (name "Net-(C17-P$2)") (class "Default")
      (node (ref "C17") (pin "2") (pinfunction "P$2_2") (pintype "bidirectional"))
      (node (ref "U19") (pin "8") (pinfunction "BYP_8") (pintype "bidirectional"))
    )
    (net (code "52") (name "Net-(C21-P$2)") (class "Default")
      (node (ref "C21") (pin "2") (pinfunction "P$2_2") (pintype "bidirectional"))
      (node (ref "D3") (pin "1") (pinfunction "V+_1") (pintype "bidirectional"))
      (node (ref "R22") (pin "P$1") (pinfunction "P$1_P$1") (pintype "bidirectional"))
      (node (ref "U6") (pin "36") (pinfunction "VREF_36") (pintype "bidirectional"))
    )
    (net (code "53") (name "Net-(C23-P$1)") (class "Default")
      (node (ref "C23") (pin "1") (pinfunction "P$1_1") (pintype "bidirectional"))
      (node (ref "U6") (pin "35") (pinfunction "COMP_35") (pintype "bidirectional"))
    )
    (net (code "54") (name "Net-(D1-PadC)") (class "Default")
      (node (ref "D1") (pin "C") (pinfunction "C_C") (pintype "bidirectional"))
      (node (ref "R2") (pin "P$1") (pinfunction "P$1_P$1") (pintype "bidirectional"))
    )
    (net (code "55") (name "Net-(D2-PadC)") (class "Default")
      (node (ref "D2") (pin "C") (pinfunction "C_C") (pintype "bidirectional"))
      (node (ref "R3") (pin "P$1") (pinfunction "P$1_P$1") (pintype "bidirectional"))
    )
    (net (code "56") (name "Net-(D4-PadC)") (class "Default")
      (node (ref "D4") (pin "C") (pinfunction "C_C") (pintype "bidirectional"))
      (node (ref "R27") (pin "P$2") (pinfunction "P$2_P$2") (pintype "bidirectional"))
    )
    (net (code "57") (name "Net-(D8-PadC)") (class "Default")
      (node (ref "D8") (pin "C") (pinfunction "C_C") (pintype "bidirectional"))
      (node (ref "R23") (pin "P$2") (pinfunction "P$2_P$2") (pintype "bidirectional"))
    )
    (net (code "58") (name "Net-(D9-PadC)") (class "Default")
      (node (ref "D9") (pin "C") (pinfunction "C_C") (pintype "bidirectional"))
      (node (ref "R24") (pin "P$2") (pinfunction "P$2_P$2") (pintype "bidirectional"))
    )
    (net (code "59") (name "Net-(J2-ICSPCLK{slash}PGC)") (class "Default")
      (node (ref "J2") (pin "5") (pinfunction "ICSPCLK/PGC_5") (pintype "bidirectional"))
      (node (ref "U7") (pin "16") (pinfunction "PGC/RG6_16") (pintype "bidirectional"))
    )
    (net (code "60") (name "Net-(J2-ICSPDAT{slash}PGD)") (class "Default")
      (node (ref "J2") (pin "4") (pinfunction "ICSPDAT/PGD_4") (pintype "bidirectional"))
      (node (ref "U7") (pin "17") (pinfunction "PGD/RB7_17") (pintype "bidirectional"))
    )
    (net (code "61") (name "Net-(J2-VPP{slash}MCLR)") (class "Default")
      (node (ref "J2") (pin "1") (pinfunction "VPP/MCLR_1") (pintype "bidirectional"))
      (node (ref "R1") (pin "P$1") (pinfunction "P$1_P$1") (pintype "bidirectional"))
      (node (ref "U7") (pin "18") (pinfunction "MCLR/VPP/RE3_18") (pintype "bidirectional"))
    )
    (net (code "62") (name "Net-(J3-D+)") (class "Default")
      (node (ref "J3") (pin "3") (pinfunction "D+_3") (pintype "bidirectional"))
      (node (ref "U9") (pin "15") (pinfunction "USBDP_15") (pintype "bidirectional"))
    )
    (net (code "63") (name "Net-(J3-D-)") (class "Default")
      (node (ref "J3") (pin "2") (pinfunction "D-_2") (pintype "bidirectional"))
      (node (ref "U9") (pin "16") (pinfunction "USBDM_16") (pintype "bidirectional"))
    )
    (net (code "64") (name "Net-(J4-TCK)") (class "Default")
      (node (ref "J4") (pin "6") (pinfunction "TCK_6") (pintype "bidirectional"))
      (node (ref "U10") (pin "109") (pinfunction "TCK_109") (pintype "bidirectional"))
    )
    (net (code "65") (name "Net-(J4-TDI)") (class "Default")
      (node (ref "J4") (pin "10") (pinfunction "TDI_10") (pintype "bidirectional"))
      (node (ref "U10") (pin "110") (pinfunction "TDI_110") (pintype "bidirectional"))
    )
    (net (code "66") (name "Net-(J4-TDO)") (class "Default")
      (node (ref "J4") (pin "8") (pinfunction "TDO_8") (pintype "bidirectional"))
      (node (ref "U10") (pin "106") (pinfunction "TDO_106") (pintype "bidirectional"))
    )
    (net (code "67") (name "Net-(J4-TMS)") (class "Default")
      (node (ref "J4") (pin "4") (pinfunction "TMS_4") (pintype "bidirectional"))
      (node (ref "U10") (pin "107") (pinfunction "TMS_107") (pintype "bidirectional"))
    )
    (net (code "68") (name "Net-(R17-PadP$2)") (class "Default")
      (node (ref "R17") (pin "P$2") (pinfunction "P$2_P$2") (pintype "bidirectional"))
      (node (ref "R18") (pin "P$1") (pinfunction "P$1_P$1") (pintype "bidirectional"))
      (node (ref "R31") (pin "P$2") (pinfunction "P$2_P$2") (pintype "bidirectional"))
    )
    (net (code "69") (name "Net-(R28-PadP$2)") (class "Default")
      (node (ref "R28") (pin "P$2") (pinfunction "P$2_P$2") (pintype "bidirectional"))
      (node (ref "R29") (pin "P$1") (pinfunction "P$1_P$1") (pintype "bidirectional"))
      (node (ref "R30") (pin "P$2") (pinfunction "P$2_P$2") (pintype "bidirectional"))
    )
    (net (code "70") (name "Net-(R32-PadP$2)") (class "Default")
      (node (ref "R32") (pin "P$2") (pinfunction "P$2_P$2") (pintype "bidirectional"))
      (node (ref "R33") (pin "P$1") (pinfunction "P$1_P$1") (pintype "bidirectional"))
      (node (ref "R34") (pin "P$2") (pinfunction "P$2_P$2") (pintype "bidirectional"))
    )
    (net (code "71") (name "Net-(R35-PadP$2)") (class "Default")
      (node (ref "R35") (pin "P$2") (pinfunction "P$2_P$2") (pintype "bidirectional"))
      (node (ref "R36") (pin "P$1") (pinfunction "P$1_P$1") (pintype "bidirectional"))
      (node (ref "R37") (pin "P$2") (pinfunction "P$2_P$2") (pintype "bidirectional"))
    )
    (net (code "72") (name "Net-(R38-PadP$2)") (class "Default")
      (node (ref "R38") (pin "P$2") (pinfunction "P$2_P$2") (pintype "bidirectional"))
      (node (ref "R39") (pin "P$1") (pinfunction "P$1_P$1") (pintype "bidirectional"))
      (node (ref "R40") (pin "P$2") (pinfunction "P$2_P$2") (pintype "bidirectional"))
    )
    (net (code "73") (name "Net-(R41-PadP$2)") (class "Default")
      (node (ref "R41") (pin "P$2") (pinfunction "P$2_P$2") (pintype "bidirectional"))
      (node (ref "R42") (pin "P$1") (pinfunction "P$1_P$1") (pintype "bidirectional"))
      (node (ref "R43") (pin "P$2") (pinfunction "P$2_P$2") (pintype "bidirectional"))
    )
    (net (code "74") (name "Net-(R44-PadP$2)") (class "Default")
      (node (ref "R44") (pin "P$2") (pinfunction "P$2_P$2") (pintype "bidirectional"))
      (node (ref "R45") (pin "P$1") (pinfunction "P$1_P$1") (pintype "bidirectional"))
      (node (ref "R46") (pin "P$2") (pinfunction "P$2_P$2") (pintype "bidirectional"))
    )
    (net (code "75") (name "Net-(R47-PadP$2)") (class "Default")
      (node (ref "R47") (pin "P$2") (pinfunction "P$2_P$2") (pintype "bidirectional"))
      (node (ref "R48") (pin "P$1") (pinfunction "P$1_P$1") (pintype "bidirectional"))
      (node (ref "R49") (pin "P$2") (pinfunction "P$2_P$2") (pintype "bidirectional"))
    )
    (net (code "76") (name "Net-(U6-RSET)") (class "Default")
      (node (ref "R11") (pin "P$2") (pinfunction "P$2_P$2") (pintype "bidirectional"))
      (node (ref "U6") (pin "37") (pinfunction "RSET_37") (pintype "bidirectional"))
    )
    (net (code "77") (name "Net-(U7-RB2)") (class "Default")
      (node (ref "D8") (pin "A") (pinfunction "A_A") (pintype "bidirectional"))
      (node (ref "U7") (pin "10") (pinfunction "RB2_10") (pintype "bidirectional"))
    )
    (net (code "78") (name "Net-(U7-RB3)") (class "Default")
      (node (ref "D9") (pin "A") (pinfunction "A_A") (pintype "bidirectional"))
      (node (ref "U7") (pin "11") (pinfunction "RB3_11") (pintype "bidirectional"))
    )
    (net (code "79") (name "Net-(U9-CBUS0)") (class "Default")
      (node (ref "R2") (pin "P$2") (pinfunction "P$2_P$2") (pintype "bidirectional"))
      (node (ref "U9") (pin "23") (pinfunction "CBUS0_23") (pintype "bidirectional"))
    )
    (net (code "80") (name "Net-(U9-CBUS1)") (class "Default")
      (node (ref "R3") (pin "P$2") (pinfunction "P$2_P$2") (pintype "bidirectional"))
      (node (ref "U9") (pin "22") (pinfunction "CBUS1_22") (pintype "bidirectional"))
    )
    (net (code "81") (name "Net-(U9-RESET#)") (class "Default")
      (node (ref "R4") (pin "P$2") (pinfunction "P$2_P$2") (pintype "bidirectional"))
      (node (ref "R5") (pin "P$1") (pinfunction "P$1_P$1") (pintype "bidirectional"))
      (node (ref "U9") (pin "19") (pinfunction "RESET#_19") (pintype "bidirectional"))
    )
    (net (code "82") (name "Net-(U10-IO_L31N_GCLK30_D15_2)") (class "Default")
      (node (ref "U10") (pin "50") (pinfunction "IO_L31N_GCLK30_D15_2_50") (pintype "bidirectional"))
      (node (ref "U12") (pin "4") (pinfunction "B_4") (pintype "bidirectional"))
    )
    (net (code "83") (name "Net-(U12-A)") (class "Default")
      (node (ref "U12") (pin "3") (pinfunction "A_3") (pintype "bidirectional"))
      (node (ref "Y1") (pin "3") (pinfunction "OUTPUT_3") (pintype "bidirectional"))
    )
    (net (code "84") (name "Net-(U13-B)") (class "Default")
      (node (ref "J5") (pin "10") (pinfunction "10_10") (pintype "bidirectional"))
      (node (ref "U13") (pin "4") (pinfunction "B_4") (pintype "bidirectional"))
    )
    (net (code "85") (name "Net-(U17-B)") (class "Default")
      (node (ref "U17") (pin "4") (pinfunction "B_4") (pintype "bidirectional"))
      (node (ref "U19") (pin "13") (pinfunction "SYNC_IN1_13") (pintype "bidirectional"))
    )
    (net (code "86") (name "Net-(U18-B)") (class "Default")
      (node (ref "U18") (pin "4") (pinfunction "B_4") (pintype "bidirectional"))
      (node (ref "U19") (pin "15") (pinfunction "SYNC_IN2_15") (pintype "bidirectional"))
    )
    (net (code "87") (name "Net-(U19-SYNC_OUT1)") (class "Default")
      (node (ref "J5") (pin "9") (pinfunction "9_9") (pintype "bidirectional"))
      (node (ref "U19") (pin "14") (pinfunction "SYNC_OUT1_14") (pintype "bidirectional"))
    )
    (net (code "88") (name "Net-(U19-SYNC_OUT2)") (class "Default")
      (node (ref "J5") (pin "7") (pinfunction "7_7") (pintype "bidirectional"))
      (node (ref "U19") (pin "16") (pinfunction "SYNC_OUT2_16") (pintype "bidirectional"))
    )
    (net (code "89") (name "PIC_D0") (class "Default")
      (node (ref "U10") (pin "131") (pinfunction "IO_L35N_GCLK16_0_131") (pintype "bidirectional"))
      (node (ref "U7") (pin "19") (pinfunction "RA0_19") (pintype "bidirectional"))
    )
    (net (code "90") (name "PIC_D1") (class "Default")
      (node (ref "U10") (pin "127") (pinfunction "IO_L36P_GCLK15_0_127") (pintype "bidirectional"))
      (node (ref "U7") (pin "20") (pinfunction "RA1_20") (pintype "bidirectional"))
    )
    (net (code "91") (name "PIC_D2") (class "Default")
      (node (ref "U10") (pin "126") (pinfunction "IO_L36N_GCLK14_0_126") (pintype "bidirectional"))
      (node (ref "U7") (pin "21") (pinfunction "RA2_21") (pintype "bidirectional"))
    )
    (net (code "92") (name "PIC_D3") (class "Default")
      (node (ref "U10") (pin "124") (pinfunction "IO_L37P_GCLK13_0_124") (pintype "bidirectional"))
      (node (ref "U7") (pin "22") (pinfunction "RA3_22") (pintype "bidirectional"))
    )
    (net (code "93") (name "PIC_D4") (class "Default")
      (node (ref "U10") (pin "123") (pinfunction "IO_L37N_GCLK12_0_123") (pintype "bidirectional"))
      (node (ref "U7") (pin "23") (pinfunction "RA4_23") (pintype "bidirectional"))
    )
    (net (code "94") (name "PIC_D5") (class "Default")
      (node (ref "U10") (pin "121") (pinfunction "IO_L62P_0_121") (pintype "bidirectional"))
      (node (ref "U7") (pin "24") (pinfunction "RA5_24") (pintype "bidirectional"))
    )
    (net (code "95") (name "PIC_D6") (class "Default")
      (node (ref "U10") (pin "119") (pinfunction "IO_L63P_SCP7_0_119") (pintype "bidirectional"))
      (node (ref "U7") (pin "31") (pinfunction "RA6_31") (pintype "bidirectional"))
    )
    (net (code "96") (name "PIC_D7") (class "Default")
      (node (ref "U10") (pin "120") (pinfunction "IO_L62N_VREF_0_120") (pintype "bidirectional"))
      (node (ref "U7") (pin "30") (pinfunction "RA7_30") (pintype "bidirectional"))
    )
    (net (code "97") (name "PIC_GPIO1") (class "Default")
      (node (ref "U10") (pin "45") (pinfunction "IO_L49N_D4_2_45") (pintype "bidirectional"))
      (node (ref "U7") (pin "4") (pinfunction "RD6_4") (pintype "bidirectional"))
    )
    (net (code "98") (name "PIC_GPIO2") (class "Default")
      (node (ref "U10") (pin "44") (pinfunction "IO_L62P_D5_2_44") (pintype "bidirectional"))
      (node (ref "U7") (pin "5") (pinfunction "RD7_5") (pintype "bidirectional"))
    )
    (net (code "99") (name "PIC_GPIO3") (class "Default")
      (node (ref "U10") (pin "43") (pinfunction "IO_L62N_D6_2_43") (pintype "bidirectional"))
      (node (ref "U7") (pin "25") (pinfunction "RE0_25") (pintype "bidirectional"))
    )
    (net (code "100") (name "PPU_A0") (class "Default")
      (node (ref "U10") (pin "67") (pinfunction "IO_L2P_CMPCLK_2_67") (pintype "bidirectional"))
      (node (ref "U2") (pin "6") (pinfunction "A4_6") (pintype "bidirectional"))
    )
    (net (code "101") (name "PPU_A1") (class "Default")
      (node (ref "U10") (pin "75") (pinfunction "IO_L74P_AWAKE_1_75") (pintype "bidirectional"))
      (node (ref "U2") (pin "5") (pinfunction "A3_5") (pintype "bidirectional"))
    )
    (net (code "102") (name "PPU_A2") (class "Default")
      (node (ref "U10") (pin "78") (pinfunction "IO_L47N_1_78") (pintype "bidirectional"))
      (node (ref "U2") (pin "4") (pinfunction "A2_4") (pintype "bidirectional"))
    )
    (net (code "103") (name "PPU_A8") (class "Default")
      (node (ref "U10") (pin "47") (pinfunction "IO_L48N_RDWR_B_VREF_2_47") (pintype "bidirectional"))
      (node (ref "U5") (pin "8") (pinfunction "A6_8") (pintype "bidirectional"))
    )
    (net (code "104") (name "PPU_A9") (class "Default")
      (node (ref "U10") (pin "48") (pinfunction "IO_L48P_D7_2_48") (pintype "bidirectional"))
      (node (ref "U5") (pin "7") (pinfunction "A5_7") (pintype "bidirectional"))
    )
    (net (code "105") (name "PPU_A10") (class "Default")
      (node (ref "U10") (pin "51") (pinfunction "IO_L31P_GCLK31_D14_2_51") (pintype "bidirectional"))
      (node (ref "U5") (pin "6") (pinfunction "A4_6") (pintype "bidirectional"))
    )
    (net (code "106") (name "PPU_A11") (class "Default")
      (node (ref "U10") (pin "55") (pinfunction "IO_L30N_GCLK0_USERCCLK_2_55") (pintype "bidirectional"))
      (node (ref "U5") (pin "5") (pinfunction "A3_5") (pintype "bidirectional"))
    )
    (net (code "107") (name "PPU_A12") (class "Default")
      (node (ref "U10") (pin "56") (pinfunction "IO_L30P_GCLK1_D13_2_56") (pintype "bidirectional"))
      (node (ref "U5") (pin "4") (pinfunction "A2_4") (pintype "bidirectional"))
    )
    (net (code "108") (name "PPU_A13") (class "Default")
      (node (ref "U10") (pin "57") (pinfunction "IO_L14N_D12_2_57") (pintype "bidirectional"))
      (node (ref "U5") (pin "3") (pinfunction "A1_3") (pintype "bidirectional"))
    )
    (net (code "109") (name "PPU_AD0") (class "Default")
      (node (ref "U1") (pin "3") (pinfunction "A1_3") (pintype "bidirectional"))
      (node (ref "U10") (pin "104") (pinfunction "IO_L1N_VREF_1_104") (pintype "bidirectional"))
    )
    (net (code "110") (name "PPU_AD1") (class "Default")
      (node (ref "U1") (pin "4") (pinfunction "A2_4") (pintype "bidirectional"))
      (node (ref "U10") (pin "102") (pinfunction "IO_L32P_1_102") (pintype "bidirectional"))
    )
    (net (code "111") (name "PPU_AD2") (class "Default")
      (node (ref "U1") (pin "5") (pinfunction "A3_5") (pintype "bidirectional"))
      (node (ref "U10") (pin "101") (pinfunction "IO_L32N_1_101") (pintype "bidirectional"))
    )
    (net (code "112") (name "PPU_AD3") (class "Default")
      (node (ref "U1") (pin "6") (pinfunction "A4_6") (pintype "bidirectional"))
      (node (ref "U10") (pin "100") (pinfunction "IO_L33P_1_100") (pintype "bidirectional"))
    )
    (net (code "113") (name "PPU_AD4") (class "Default")
      (node (ref "U1") (pin "7") (pinfunction "A5_7") (pintype "bidirectional"))
      (node (ref "U10") (pin "99") (pinfunction "IO_L33N_1_99") (pintype "bidirectional"))
    )
    (net (code "114") (name "PPU_AD5") (class "Default")
      (node (ref "U1") (pin "8") (pinfunction "A6_8") (pintype "bidirectional"))
      (node (ref "U10") (pin "98") (pinfunction "IO_L34P_1_98") (pintype "bidirectional"))
    )
    (net (code "115") (name "PPU_AD6") (class "Default")
      (node (ref "U1") (pin "9") (pinfunction "A7_9") (pintype "bidirectional"))
      (node (ref "U10") (pin "97") (pinfunction "IO_L34N_1_97") (pintype "bidirectional"))
    )
    (net (code "116") (name "PPU_AD7") (class "Default")
      (node (ref "U1") (pin "10") (pinfunction "A8_10") (pintype "bidirectional"))
      (node (ref "U10") (pin "95") (pinfunction "IO_L40P_GCLK11_1_95") (pintype "bidirectional"))
    )
    (net (code "117") (name "PPU_AD_DIR") (class "Default")
      (node (ref "U1") (pin "2") (pinfunction "DIR_2") (pintype "bidirectional"))
      (node (ref "U10") (pin "105") (pinfunction "IO_L1P_1_105") (pintype "bidirectional"))
    )
    (net (code "118") (name "PPU_ALE") (class "Default")
      (node (ref "U10") (pin "46") (pinfunction "IO_L49P_D3_2_46") (pintype "bidirectional"))
      (node (ref "U5") (pin "9") (pinfunction "A7_9") (pintype "bidirectional"))
    )
    (net (code "119") (name "PPU_BUFF_OE") (class "Default")
      (node (ref "U1") (pin "22") (pinfunction "OE_22") (pintype "bidirectional"))
      (node (ref "U10") (pin "80") (pinfunction "IO_L46N_1_80") (pintype "bidirectional"))
      (node (ref "U2") (pin "22") (pinfunction "OE_22") (pintype "bidirectional"))
      (node (ref "U3") (pin "22") (pinfunction "OE_22") (pintype "bidirectional"))
      (node (ref "U4") (pin "22") (pinfunction "OE_22") (pintype "bidirectional"))
      (node (ref "U5") (pin "22") (pinfunction "OE_22") (pintype "bidirectional"))
    )
    (net (code "120") (name "PPU_CLK") (class "Default")
      (node (ref "U10") (pin "88") (pinfunction "IO_L42P_GCLK7_1_88") (pintype "bidirectional"))
      (node (ref "U2") (pin "9") (pinfunction "A7_9") (pintype "bidirectional"))
    )
    (net (code "121") (name "PPU_D0") (class "Default")
      (node (ref "U10") (pin "93") (pinfunction "IO_L41P_GCLK9_IRDY1_1_93") (pintype "bidirectional"))
      (node (ref "U3") (pin "3") (pinfunction "A1_3") (pintype "bidirectional"))
    )
    (net (code "122") (name "PPU_D1") (class "Default")
      (node (ref "U10") (pin "92") (pinfunction "IO_L41N_GCLK8_1_92") (pintype "bidirectional"))
      (node (ref "U3") (pin "4") (pinfunction "A2_4") (pintype "bidirectional"))
    )
    (net (code "123") (name "PPU_D2") (class "Default")
      (node (ref "U10") (pin "87") (pinfunction "IO_L42N_GCLK6_TRDY1_1_87") (pintype "bidirectional"))
      (node (ref "U3") (pin "5") (pinfunction "A3_5") (pintype "bidirectional"))
    )
    (net (code "124") (name "PPU_D3") (class "Default")
      (node (ref "U10") (pin "85") (pinfunction "IO_L43P_GCLK5_1_85") (pintype "bidirectional"))
      (node (ref "U3") (pin "6") (pinfunction "A4_6") (pintype "bidirectional"))
    )
    (net (code "125") (name "PPU_D4") (class "Default")
      (node (ref "U10") (pin "84") (pinfunction "IO_L43N_GCLK4_1_84") (pintype "bidirectional"))
      (node (ref "U3") (pin "7") (pinfunction "A5_7") (pintype "bidirectional"))
    )
    (net (code "126") (name "PPU_D5") (class "Default")
      (node (ref "U10") (pin "83") (pinfunction "IO_L45P_1_83") (pintype "bidirectional"))
      (node (ref "U3") (pin "8") (pinfunction "A6_8") (pintype "bidirectional"))
    )
    (net (code "127") (name "PPU_D6") (class "Default")
      (node (ref "U10") (pin "82") (pinfunction "IO_L45N_1_82") (pintype "bidirectional"))
      (node (ref "U3") (pin "9") (pinfunction "A7_9") (pintype "bidirectional"))
    )
    (net (code "128") (name "PPU_D7") (class "Default")
      (node (ref "U10") (pin "81") (pinfunction "IO_L46P_1_81") (pintype "bidirectional"))
      (node (ref "U3") (pin "10") (pinfunction "A8_10") (pintype "bidirectional"))
    )
    (net (code "129") (name "PPU_D_DIR") (class "Default")
      (node (ref "U10") (pin "94") (pinfunction "IO_L40N_GCLK10_1_94") (pintype "bidirectional"))
      (node (ref "U3") (pin "2") (pinfunction "DIR_2") (pintype "bidirectional"))
    )
    (net (code "130") (name "PPU_R{slash}W") (class "Default")
      (node (ref "U10") (pin "79") (pinfunction "IO_L47P_1_79") (pintype "bidirectional"))
      (node (ref "U2") (pin "3") (pinfunction "A1_3") (pintype "bidirectional"))
    )
    (net (code "131") (name "PPU_{slash}CS") (class "Default")
      (node (ref "U10") (pin "66") (pinfunction "IO_L2N_CMPMOSI_2_66") (pintype "bidirectional"))
      (node (ref "U2") (pin "7") (pinfunction "A5_7") (pintype "bidirectional"))
    )
    (net (code "132") (name "PPU_{slash}INT") (class "Default")
      (node (ref "U10") (pin "58") (pinfunction "IO_L14P_D11_2_58") (pintype "bidirectional"))
      (node (ref "U4") (pin "10") (pinfunction "A8_10") (pintype "bidirectional"))
    )
    (net (code "133") (name "PPU_{slash}RD") (class "Default")
      (node (ref "U10") (pin "61") (pinfunction "IO_L12N_D2_MISO3_2_61") (pintype "bidirectional"))
      (node (ref "U4") (pin "5") (pinfunction "A3_5") (pintype "bidirectional"))
    )
    (net (code "134") (name "PPU_{slash}RST") (class "Default")
      (node (ref "U10") (pin "62") (pinfunction "IO_L12P_D1_MISO2_2_62") (pintype "bidirectional"))
      (node (ref "U2") (pin "8") (pinfunction "A6_8") (pintype "bidirectional"))
    )
    (net (code "135") (name "PPU_{slash}WR") (class "Default")
      (node (ref "U10") (pin "59") (pinfunction "IO_L13N_D10_2_59") (pintype "bidirectional"))
      (node (ref "U4") (pin "6") (pinfunction "A4_6") (pintype "bidirectional"))
    )
    (net (code "136") (name "R{slash}W") (class "Default")
      (node (ref "J1") (pin "1") (pinfunction "1_1") (pintype "bidirectional"))
      (node (ref "U2") (pin "21") (pinfunction "B1_21") (pintype "bidirectional"))
    )
    (net (code "137") (name "USB_CTS") (class "Default")
      (node (ref "U7") (pin "39") (pinfunction "RD1_39") (pintype "bidirectional"))
      (node (ref "U9") (pin "11") (pinfunction "CTS#_11") (pintype "bidirectional"))
    )
    (net (code "138") (name "USB_PWREN") (class "Default")
      (node (ref "U7") (pin "9") (pinfunction "RB1_9") (pintype "bidirectional"))
      (node (ref "U9") (pin "14") (pinfunction "CBUS3_14") (pintype "bidirectional"))
    )
    (net (code "139") (name "USB_RTS") (class "Default")
      (node (ref "U7") (pin "8") (pinfunction "RB0_8") (pintype "bidirectional"))
      (node (ref "U9") (pin "3") (pinfunction "RTS#_3") (pintype "bidirectional"))
    )
    (net (code "140") (name "USB_RXD") (class "Default")
      (node (ref "U7") (pin "44") (pinfunction "RC6_44") (pintype "bidirectional"))
      (node (ref "U9") (pin "5") (pinfunction "RXD_5") (pintype "bidirectional"))
    )
    (net (code "141") (name "USB_TXD") (class "Default")
      (node (ref "U7") (pin "1") (pinfunction "RC7_1") (pintype "bidirectional"))
      (node (ref "U9") (pin "1") (pinfunction "TXD_1") (pintype "bidirectional"))
    )
    (net (code "142") (name "VIDEO_B0") (class "Default")
      (node (ref "U10") (pin "10") (pinfunction "IO_L50P_3_10") (pintype "bidirectional"))
      (node (ref "U6") (pin "16") (pinfunction "B0_16") (pintype "bidirectional"))
    )
    (net (code "143") (name "VIDEO_B1") (class "Default")
      (node (ref "U10") (pin "9") (pinfunction "IO_L50N_3_9") (pintype "bidirectional"))
      (node (ref "U6") (pin "17") (pinfunction "B1_17") (pintype "bidirectional"))
    )
    (net (code "144") (name "VIDEO_B2") (class "Default")
      (node (ref "U10") (pin "8") (pinfunction "IO_L51P_3_8") (pintype "bidirectional"))
      (node (ref "U6") (pin "18") (pinfunction "B2_18") (pintype "bidirectional"))
    )
    (net (code "145") (name "VIDEO_B3") (class "Default")
      (node (ref "U10") (pin "7") (pinfunction "IO_L51N_3_7") (pintype "bidirectional"))
      (node (ref "U6") (pin "19") (pinfunction "B3_19") (pintype "bidirectional"))
    )
    (net (code "146") (name "VIDEO_B4") (class "Default")
      (node (ref "U10") (pin "6") (pinfunction "IO_L52P_3_6") (pintype "bidirectional"))
      (node (ref "U6") (pin "20") (pinfunction "B4_20") (pintype "bidirectional"))
    )
    (net (code "147") (name "VIDEO_B5") (class "Default")
      (node (ref "U10") (pin "5") (pinfunction "IO_L52N_3_5") (pintype "bidirectional"))
      (node (ref "U6") (pin "21") (pinfunction "B5_21") (pintype "bidirectional"))
    )
    (net (code "148") (name "VIDEO_B6") (class "Default")
      (node (ref "U10") (pin "2") (pinfunction "IO_L83P_3_2") (pintype "bidirectional"))
      (node (ref "U6") (pin "22") (pinfunction "B6_22") (pintype "bidirectional"))
    )
    (net (code "149") (name "VIDEO_B7") (class "Default")
      (node (ref "U10") (pin "1") (pinfunction "IO_L83N_VREF_3_1") (pintype "bidirectional"))
      (node (ref "U6") (pin "23") (pinfunction "B7_23") (pintype "bidirectional"))
    )
    (net (code "150") (name "VIDEO_CLOCK") (class "Default")
      (node (ref "U10") (pin "134") (pinfunction "IO_L34P_GCLK19_0_134") (pintype "bidirectional"))
      (node (ref "U6") (pin "24") (pinfunction "CLOCK_24") (pintype "bidirectional"))
    )
    (net (code "151") (name "VIDEO_G0") (class "Default")
      (node (ref "U10") (pin "24") (pinfunction "IO_L41P_GCLK27_3_24") (pintype "bidirectional"))
      (node (ref "U6") (pin "3") (pinfunction "G0_3") (pintype "bidirectional"))
    )
    (net (code "152") (name "VIDEO_G1") (class "Default")
      (node (ref "U10") (pin "23") (pinfunction "IO_L41N_GCLK26_3_23") (pintype "bidirectional"))
      (node (ref "U6") (pin "4") (pinfunction "G1_4") (pintype "bidirectional"))
    )
    (net (code "153") (name "VIDEO_G2") (class "Default")
      (node (ref "U10") (pin "22") (pinfunction "IO_L42P_GCLK25_TRDY2_3_22") (pintype "bidirectional"))
      (node (ref "U6") (pin "5") (pinfunction "G2_5") (pintype "bidirectional"))
    )
    (net (code "154") (name "VIDEO_G3") (class "Default")
      (node (ref "U10") (pin "21") (pinfunction "IO_L42N_GCLK24_3_21") (pintype "bidirectional"))
      (node (ref "U6") (pin "6") (pinfunction "G3_6") (pintype "bidirectional"))
    )
    (net (code "155") (name "VIDEO_G4") (class "Default")
      (node (ref "U10") (pin "17") (pinfunction "IO_L43P_GCLK23_3_17") (pintype "bidirectional"))
      (node (ref "U6") (pin "7") (pinfunction "G4_7") (pintype "bidirectional"))
    )
    (net (code "156") (name "VIDEO_G5") (class "Default")
      (node (ref "U10") (pin "16") (pinfunction "IO_L43N_GCLK22_IRDY2_3_16") (pintype "bidirectional"))
      (node (ref "U6") (pin "8") (pinfunction "G5_8") (pintype "bidirectional"))
    )
    (net (code "157") (name "VIDEO_G6") (class "Default")
      (node (ref "U10") (pin "15") (pinfunction "IO_L44P_GCLK21_3_15") (pintype "bidirectional"))
      (node (ref "U6") (pin "9") (pinfunction "G6_9") (pintype "bidirectional"))
    )
    (net (code "158") (name "VIDEO_G7") (class "Default")
      (node (ref "U10") (pin "14") (pinfunction "IO_L44N_GCLK20_3_14") (pintype "bidirectional"))
      (node (ref "U6") (pin "10") (pinfunction "G7_10") (pintype "bidirectional"))
    )
    (net (code "159") (name "VIDEO_OUT_BLUE") (class "Default")
      (node (ref "J5") (pin "1") (pinfunction "1_1") (pintype "bidirectional"))
      (node (ref "R14") (pin "P$2") (pinfunction "P$2_P$2") (pintype "bidirectional"))
      (node (ref "U19") (pin "3") (pinfunction "VIDEO1_3") (pintype "bidirectional"))
      (node (ref "U6") (pin "28") (pinfunction "IOB_28") (pintype "bidirectional"))
    )
    (net (code "160") (name "VIDEO_OUT_GREEN") (class "Default")
      (node (ref "J5") (pin "3") (pinfunction "3_3") (pintype "bidirectional"))
      (node (ref "R13") (pin "P$2") (pinfunction "P$2_P$2") (pintype "bidirectional"))
      (node (ref "U19") (pin "4") (pinfunction "VIDEO2_4") (pintype "bidirectional"))
      (node (ref "U6") (pin "32") (pinfunction "IOG_32") (pintype "bidirectional"))
    )
    (net (code "161") (name "VIDEO_OUT_RED") (class "Default")
      (node (ref "J5") (pin "5") (pinfunction "5_5") (pintype "bidirectional"))
      (node (ref "R12") (pin "P$2") (pinfunction "P$2_P$2") (pintype "bidirectional"))
      (node (ref "U19") (pin "5") (pinfunction "VIDEO3_5") (pintype "bidirectional"))
      (node (ref "U6") (pin "34") (pinfunction "IOR_34") (pintype "bidirectional"))
    )
    (net (code "162") (name "VIDEO_R0") (class "Default")
      (node (ref "U10") (pin "35") (pinfunction "IO_L1P_3_35") (pintype "bidirectional"))
      (node (ref "U6") (pin "41") (pinfunction "R0_41") (pintype "bidirectional"))
    )
    (net (code "163") (name "VIDEO_R1") (class "Default")
      (node (ref "U10") (pin "34") (pinfunction "IO_L1N_VREF_3_34") (pintype "bidirectional"))
      (node (ref "U6") (pin "42") (pinfunction "R1_42") (pintype "bidirectional"))
    )
    (net (code "164") (name "VIDEO_R2") (class "Default")
      (node (ref "U10") (pin "33") (pinfunction "IO_L2P_3_33") (pintype "bidirectional"))
      (node (ref "U6") (pin "43") (pinfunction "R2_43") (pintype "bidirectional"))
    )
    (net (code "165") (name "VIDEO_R3") (class "Default")
      (node (ref "U10") (pin "32") (pinfunction "IO_L2N_3_32") (pintype "bidirectional"))
      (node (ref "U6") (pin "44") (pinfunction "R3_44") (pintype "bidirectional"))
    )
    (net (code "166") (name "VIDEO_R4") (class "Default")
      (node (ref "U10") (pin "30") (pinfunction "IO_L36P_3_30") (pintype "bidirectional"))
      (node (ref "U6") (pin "45") (pinfunction "R4_45") (pintype "bidirectional"))
    )
    (net (code "167") (name "VIDEO_R5") (class "Default")
      (node (ref "U10") (pin "29") (pinfunction "IO_L36N_3_29") (pintype "bidirectional"))
      (node (ref "U6") (pin "46") (pinfunction "R5_46") (pintype "bidirectional"))
    )
    (net (code "168") (name "VIDEO_R6") (class "Default")
      (node (ref "U10") (pin "27") (pinfunction "IO_L37P_3_27") (pintype "bidirectional"))
      (node (ref "U6") (pin "47") (pinfunction "R6_47") (pintype "bidirectional"))
    )
    (net (code "169") (name "VIDEO_R7") (class "Default")
      (node (ref "U10") (pin "26") (pinfunction "IO_L37N_3_26") (pintype "bidirectional"))
      (node (ref "U6") (pin "48") (pinfunction "R7_48") (pintype "bidirectional"))
    )
    (net (code "170") (name "VIDEO_{slash}BLANK") (class "Default")
      (node (ref "U10") (pin "12") (pinfunction "IO_L49P_3_12") (pintype "bidirectional"))
      (node (ref "U6") (pin "11") (pinfunction "/BLANK_11") (pintype "bidirectional"))
    )
    (net (code "171") (name "VIDEO_{slash}SYNC") (class "Default")
      (node (ref "U10") (pin "11") (pinfunction "IO_L49N_3_11") (pintype "bidirectional"))
      (node (ref "U6") (pin "12") (pinfunction "/SYNC_12") (pintype "bidirectional"))
    )
    (net (code "172") (name "VID_ONEWIRE") (class "Default")
      (node (ref "U13") (pin "3") (pinfunction "A_3") (pintype "bidirectional"))
      (node (ref "U7") (pin "14") (pinfunction "RB4_14") (pintype "bidirectional"))
    )
    (net (code "173") (name "VID_ONEWIRE_DIR") (class "Default")
      (node (ref "U13") (pin "5") (pinfunction "DIR_5") (pintype "bidirectional"))
      (node (ref "U7") (pin "15") (pinfunction "RB5_15") (pintype "bidirectional"))
    )
    (net (code "174") (name "VSYNC") (class "Default")
      (node (ref "U10") (pin "40") (pinfunction "IO_L64N_D9_2_40") (pintype "bidirectional"))
      (node (ref "U18") (pin "3") (pinfunction "A_3") (pintype "bidirectional"))
    )
    (net (code "175") (name "unconnected-(J1-Pad14)") (class "Default")
      (node (ref "J1") (pin "14") (pinfunction "14_14") (pintype "bidirectional"))
    )
    (net (code "176") (name "unconnected-(J1-Pad15)") (class "Default")
      (node (ref "J1") (pin "15") (pinfunction "15_15") (pintype "bidirectional"))
    )
    (net (code "177") (name "unconnected-(J1-Pad16)") (class "Default")
      (node (ref "J1") (pin "16") (pinfunction "16_16") (pintype "bidirectional"))
    )
    (net (code "178") (name "unconnected-(J1-Pad17)") (class "Default")
      (node (ref "J1") (pin "17") (pinfunction "17_17") (pintype "bidirectional"))
    )
    (net (code "179") (name "unconnected-(J1-Pad21)") (class "Default")
      (node (ref "J1") (pin "21") (pinfunction "21_21") (pintype "bidirectional"))
    )
    (net (code "180") (name "unconnected-(J2-LVP-Pad6)") (class "Default")
      (node (ref "J2") (pin "6") (pinfunction "LVP_6") (pintype "bidirectional"))
    )
    (net (code "181") (name "unconnected-(U2-A8-Pad10)") (class "Default")
      (node (ref "U2") (pin "10") (pinfunction "A8_10") (pintype "bidirectional"))
    )
    (net (code "182") (name "unconnected-(U4-A1-Pad3)") (class "Default")
      (node (ref "U4") (pin "3") (pinfunction "A1_3") (pintype "bidirectional"))
    )
    (net (code "183") (name "unconnected-(U4-B1-Pad21)") (class "Default")
      (node (ref "U4") (pin "21") (pinfunction "B1_21") (pintype "bidirectional"))
    )
    (net (code "184") (name "unconnected-(U4-B2-Pad20)") (class "Default")
      (node (ref "U4") (pin "20") (pinfunction "B2_20") (pintype "bidirectional"))
    )
    (net (code "185") (name "unconnected-(U4-B5-Pad17)") (class "Default")
      (node (ref "U4") (pin "17") (pinfunction "B5_17") (pintype "bidirectional"))
    )
    (net (code "186") (name "unconnected-(U4-B6-Pad16)") (class "Default")
      (node (ref "U4") (pin "16") (pinfunction "B6_16") (pintype "bidirectional"))
    )
    (net (code "187") (name "unconnected-(U4-B7-Pad15)") (class "Default")
      (node (ref "U4") (pin "15") (pinfunction "B7_15") (pintype "bidirectional"))
    )
    (net (code "188") (name "unconnected-(U5-B8-Pad14)") (class "Default")
      (node (ref "U5") (pin "14") (pinfunction "B8_14") (pintype "bidirectional"))
    )
    (net (code "189") (name "unconnected-(U7-RD5-Pad3)") (class "Default")
      (node (ref "U7") (pin "3") (pinfunction "RD5_3") (pintype "bidirectional"))
    )
    (net (code "190") (name "unconnected-(U7-RE1-Pad26)") (class "Default")
      (node (ref "U7") (pin "26") (pinfunction "RE1_26") (pintype "bidirectional"))
    )
    (net (code "191") (name "unconnected-(U7-RE2-Pad27)") (class "Default")
      (node (ref "U7") (pin "27") (pinfunction "RE2_27") (pintype "bidirectional"))
    )
    (net (code "192") (name "unconnected-(U9-CBUS2-Pad13)") (class "Default")
      (node (ref "U9") (pin "13") (pinfunction "CBUS2_13") (pintype "bidirectional"))
    )
    (net (code "193") (name "unconnected-(U9-CBUS4-Pad12)") (class "Default")
      (node (ref "U9") (pin "12") (pinfunction "CBUS4_12") (pintype "bidirectional"))
    )
    (net (code "194") (name "unconnected-(U9-DCD#-Pad10)") (class "Default")
      (node (ref "U9") (pin "10") (pinfunction "DCD#_10") (pintype "bidirectional"))
    )
    (net (code "195") (name "unconnected-(U9-DSR#-Pad9)") (class "Default")
      (node (ref "U9") (pin "9") (pinfunction "DSR#_9") (pintype "bidirectional"))
    )
    (net (code "196") (name "unconnected-(U9-DTR#-Pad2)") (class "Default")
      (node (ref "U9") (pin "2") (pinfunction "DTR#_2") (pintype "bidirectional"))
    )
    (net (code "197") (name "unconnected-(U9-OSCI-Pad27)") (class "Default")
      (node (ref "U9") (pin "27") (pinfunction "OSCI_27") (pintype "bidirectional"))
    )
    (net (code "198") (name "unconnected-(U9-OSCO-Pad28)") (class "Default")
      (node (ref "U9") (pin "28") (pinfunction "OSCO_28") (pintype "bidirectional"))
    )
    (net (code "199") (name "unconnected-(U9-RI#-Pad6)") (class "Default")
      (node (ref "U9") (pin "6") (pinfunction "RI#_6") (pintype "bidirectional"))
    )
    (net (code "200") (name "unconnected-(U10-CMPCS_B_2-Pad72)") (class "Default")
      (node (ref "U10") (pin "72") (pinfunction "CMPCS_B_2_72") (pintype "bidirectional"))
    )
    (net (code "201") (name "unconnected-(U10-IO_L1N_VREF_0-Pad143)") (class "Default")
      (node (ref "U10") (pin "143") (pinfunction "IO_L1N_VREF_0_143") (pintype "bidirectional"))
    )
    (net (code "202") (name "unconnected-(U10-IO_L2N_0-Pad141)") (class "Default")
      (node (ref "U10") (pin "141") (pinfunction "IO_L2N_0_141") (pintype "bidirectional"))
    )
    (net (code "203") (name "unconnected-(U10-IO_L2P_0-Pad142)") (class "Default")
      (node (ref "U10") (pin "142") (pinfunction "IO_L2P_0_142") (pintype "bidirectional"))
    )
    (net (code "204") (name "unconnected-(U10-IO_L3N_0-Pad139)") (class "Default")
      (node (ref "U10") (pin "139") (pinfunction "IO_L3N_0_139") (pintype "bidirectional"))
    )
    (net (code "205") (name "unconnected-(U10-IO_L3N_MOSI_CSI_B_MISO0_2-Pad64)") (class "Default")
      (node (ref "U10") (pin "64") (pinfunction "IO_L3N_MOSI_CSI_B_MISO0_2_64") (pintype "bidirectional"))
    )
    (net (code "206") (name "unconnected-(U10-IO_L3P_0-Pad140)") (class "Default")
      (node (ref "U10") (pin "140") (pinfunction "IO_L3P_0_140") (pintype "bidirectional"))
    )
    (net (code "207") (name "unconnected-(U10-IO_L4N_0-Pad137)") (class "Default")
      (node (ref "U10") (pin "137") (pinfunction "IO_L4N_0_137") (pintype "bidirectional"))
    )
    (net (code "208") (name "unconnected-(U10-IO_L4P_0-Pad138)") (class "Default")
      (node (ref "U10") (pin "138") (pinfunction "IO_L4P_0_138") (pintype "bidirectional"))
    )
    (net (code "209") (name "unconnected-(U10-IO_L34N_GCLK18_0-Pad133)") (class "Default")
      (node (ref "U10") (pin "133") (pinfunction "IO_L34N_GCLK18_0_133") (pintype "bidirectional"))
    )
    (net (code "210") (name "unconnected-(U10-IO_L35P_GCLK17_0-Pad132)") (class "Default")
      (node (ref "U10") (pin "132") (pinfunction "IO_L35P_GCLK17_0_132") (pintype "bidirectional"))
    )
    (net (code "211") (name "unconnected-(U10-IO_L65N_CSO_B_2-Pad38)") (class "Default")
      (node (ref "U10") (pin "38") (pinfunction "IO_L65N_CSO_B_2_38") (pintype "bidirectional"))
    )
    (net (code "212") (name "unconnected-(U10-IO_L66N_SCP0_0-Pad111)") (class "Default")
      (node (ref "U10") (pin "111") (pinfunction "IO_L66N_SCP0_0_111") (pintype "bidirectional"))
    )
    (net (code "213") (name "unconnected-(U10-IO_L74N_DOUT_BUSY_1-Pad74)") (class "Default")
      (node (ref "U10") (pin "74") (pinfunction "IO_L74N_DOUT_BUSY_1_74") (pintype "bidirectional"))
    )
    (net (code "214") (name "unconnected-(U19-DDC_OUT1-Pad9)") (class "Default")
      (node (ref "U19") (pin "9") (pinfunction "DDC_OUT1_9") (pintype "bidirectional"))
    )
    (net (code "215") (name "unconnected-(U19-DDC_OUT2-Pad12)") (class "Default")
      (node (ref "U19") (pin "12") (pinfunction "DDC_OUT2_12") (pintype "bidirectional"))
    )
    (net (code "216") (name "unconnected-(U19-VCC_DDC-Pad7)") (class "Default")
      (node (ref "U19") (pin "7") (pinfunction "VCC_DDC_7") (pintype "bidirectional"))
    )
    (net (code "217") (name "unconnected-(Y1-OE-Pad1)") (class "Default")
      (node (ref "Y1") (pin "1") (pinfunction "OE_1") (pintype "bidirectional"))
    )
    (net (code "218") (name "{slash}CS") (class "Default")
      (node (ref "J1") (pin "13") (pinfunction "13_13") (pintype "bidirectional"))
      (node (ref "U2") (pin "17") (pinfunction "B5_17") (pintype "bidirectional"))
    )
    (net (code "219") (name "{slash}INT") (class "Default")
      (node (ref "J1") (pin "19") (pinfunction "19_19") (pintype "bidirectional"))
      (node (ref "U4") (pin "14") (pinfunction "B8_14") (pintype "bidirectional"))
    )
    (net (code "220") (name "{slash}RD") (class "Default")
      (node (ref "J1") (pin "24") (pinfunction "24_24") (pintype "bidirectional"))
      (node (ref "U4") (pin "19") (pinfunction "B3_19") (pintype "bidirectional"))
    )
    (net (code "221") (name "{slash}RST") (class "Default")
      (node (ref "J1") (pin "22") (pinfunction "22_22") (pintype "bidirectional"))
      (node (ref "U2") (pin "16") (pinfunction "B6_16") (pintype "bidirectional"))
    )
    (net (code "222") (name "{slash}WR") (class "Default")
      (node (ref "J1") (pin "23") (pinfunction "23_23") (pintype "bidirectional"))
      (node (ref "U4") (pin "18") (pinfunction "B4_18") (pintype "bidirectional"))
    )
  )
)
